# StepperBoard.net
KiCad netlist of a schematic drawn in EAGLE
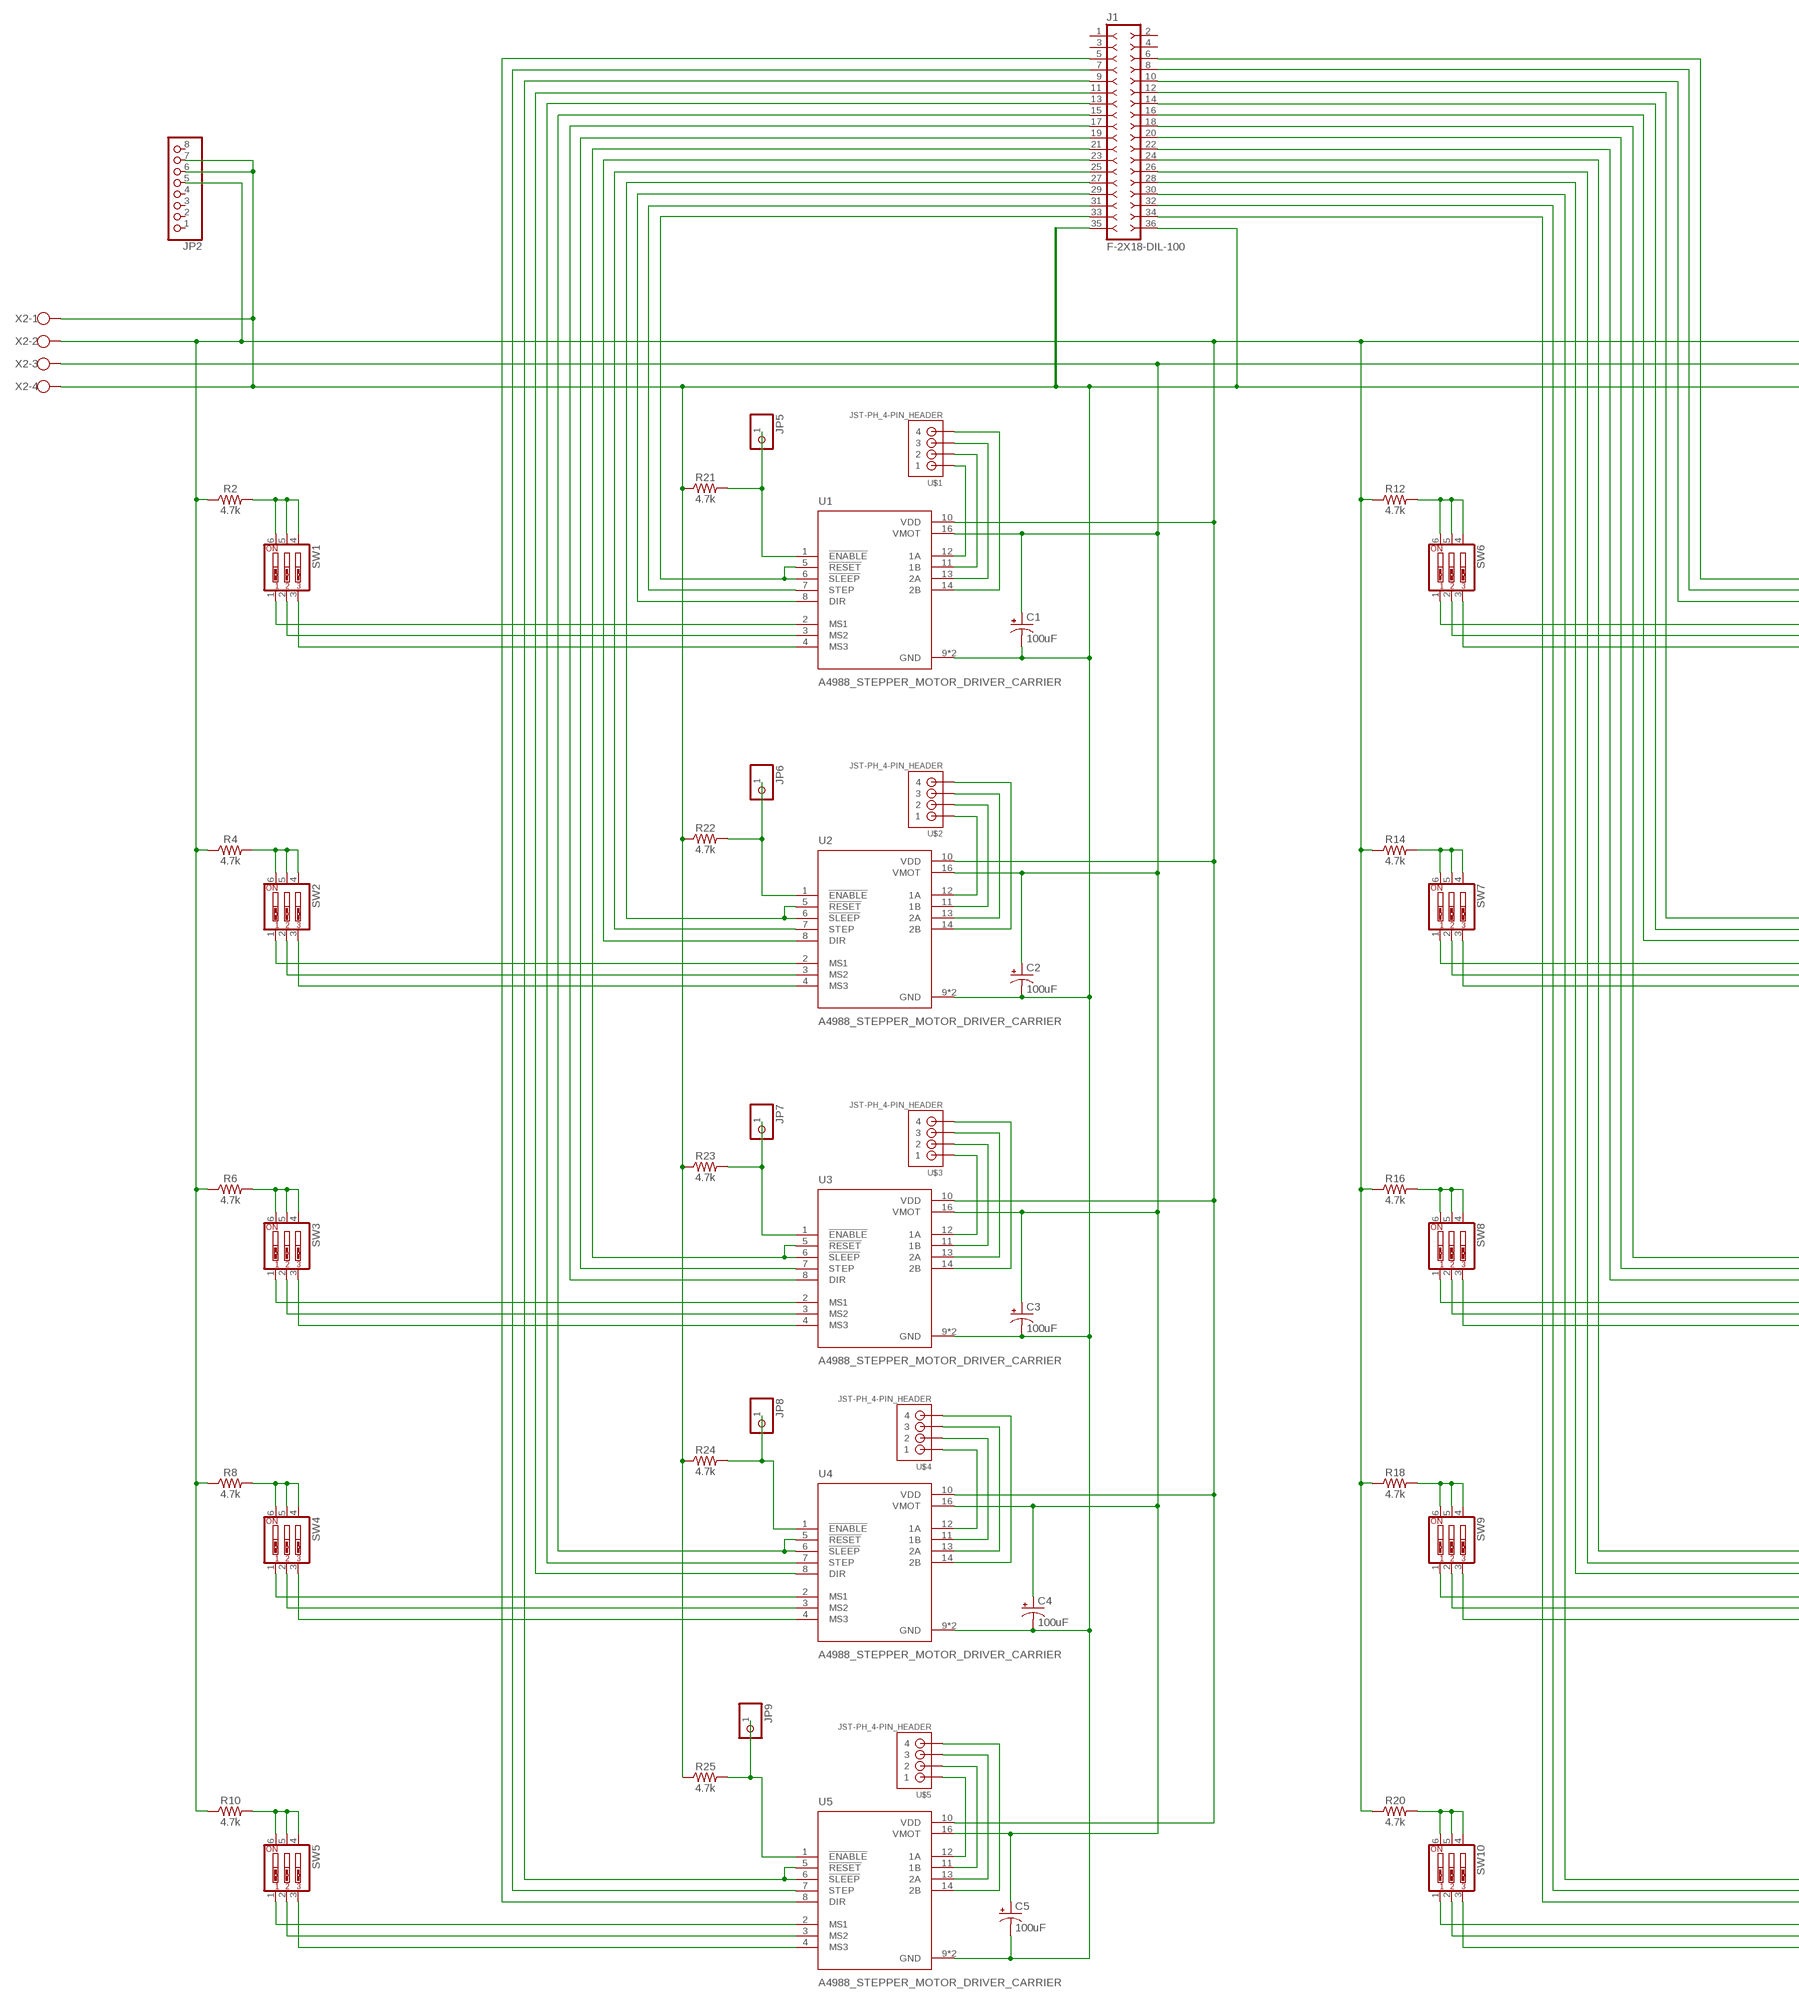
[diagram p0: schematic, sheet 1, part 1 of 2]
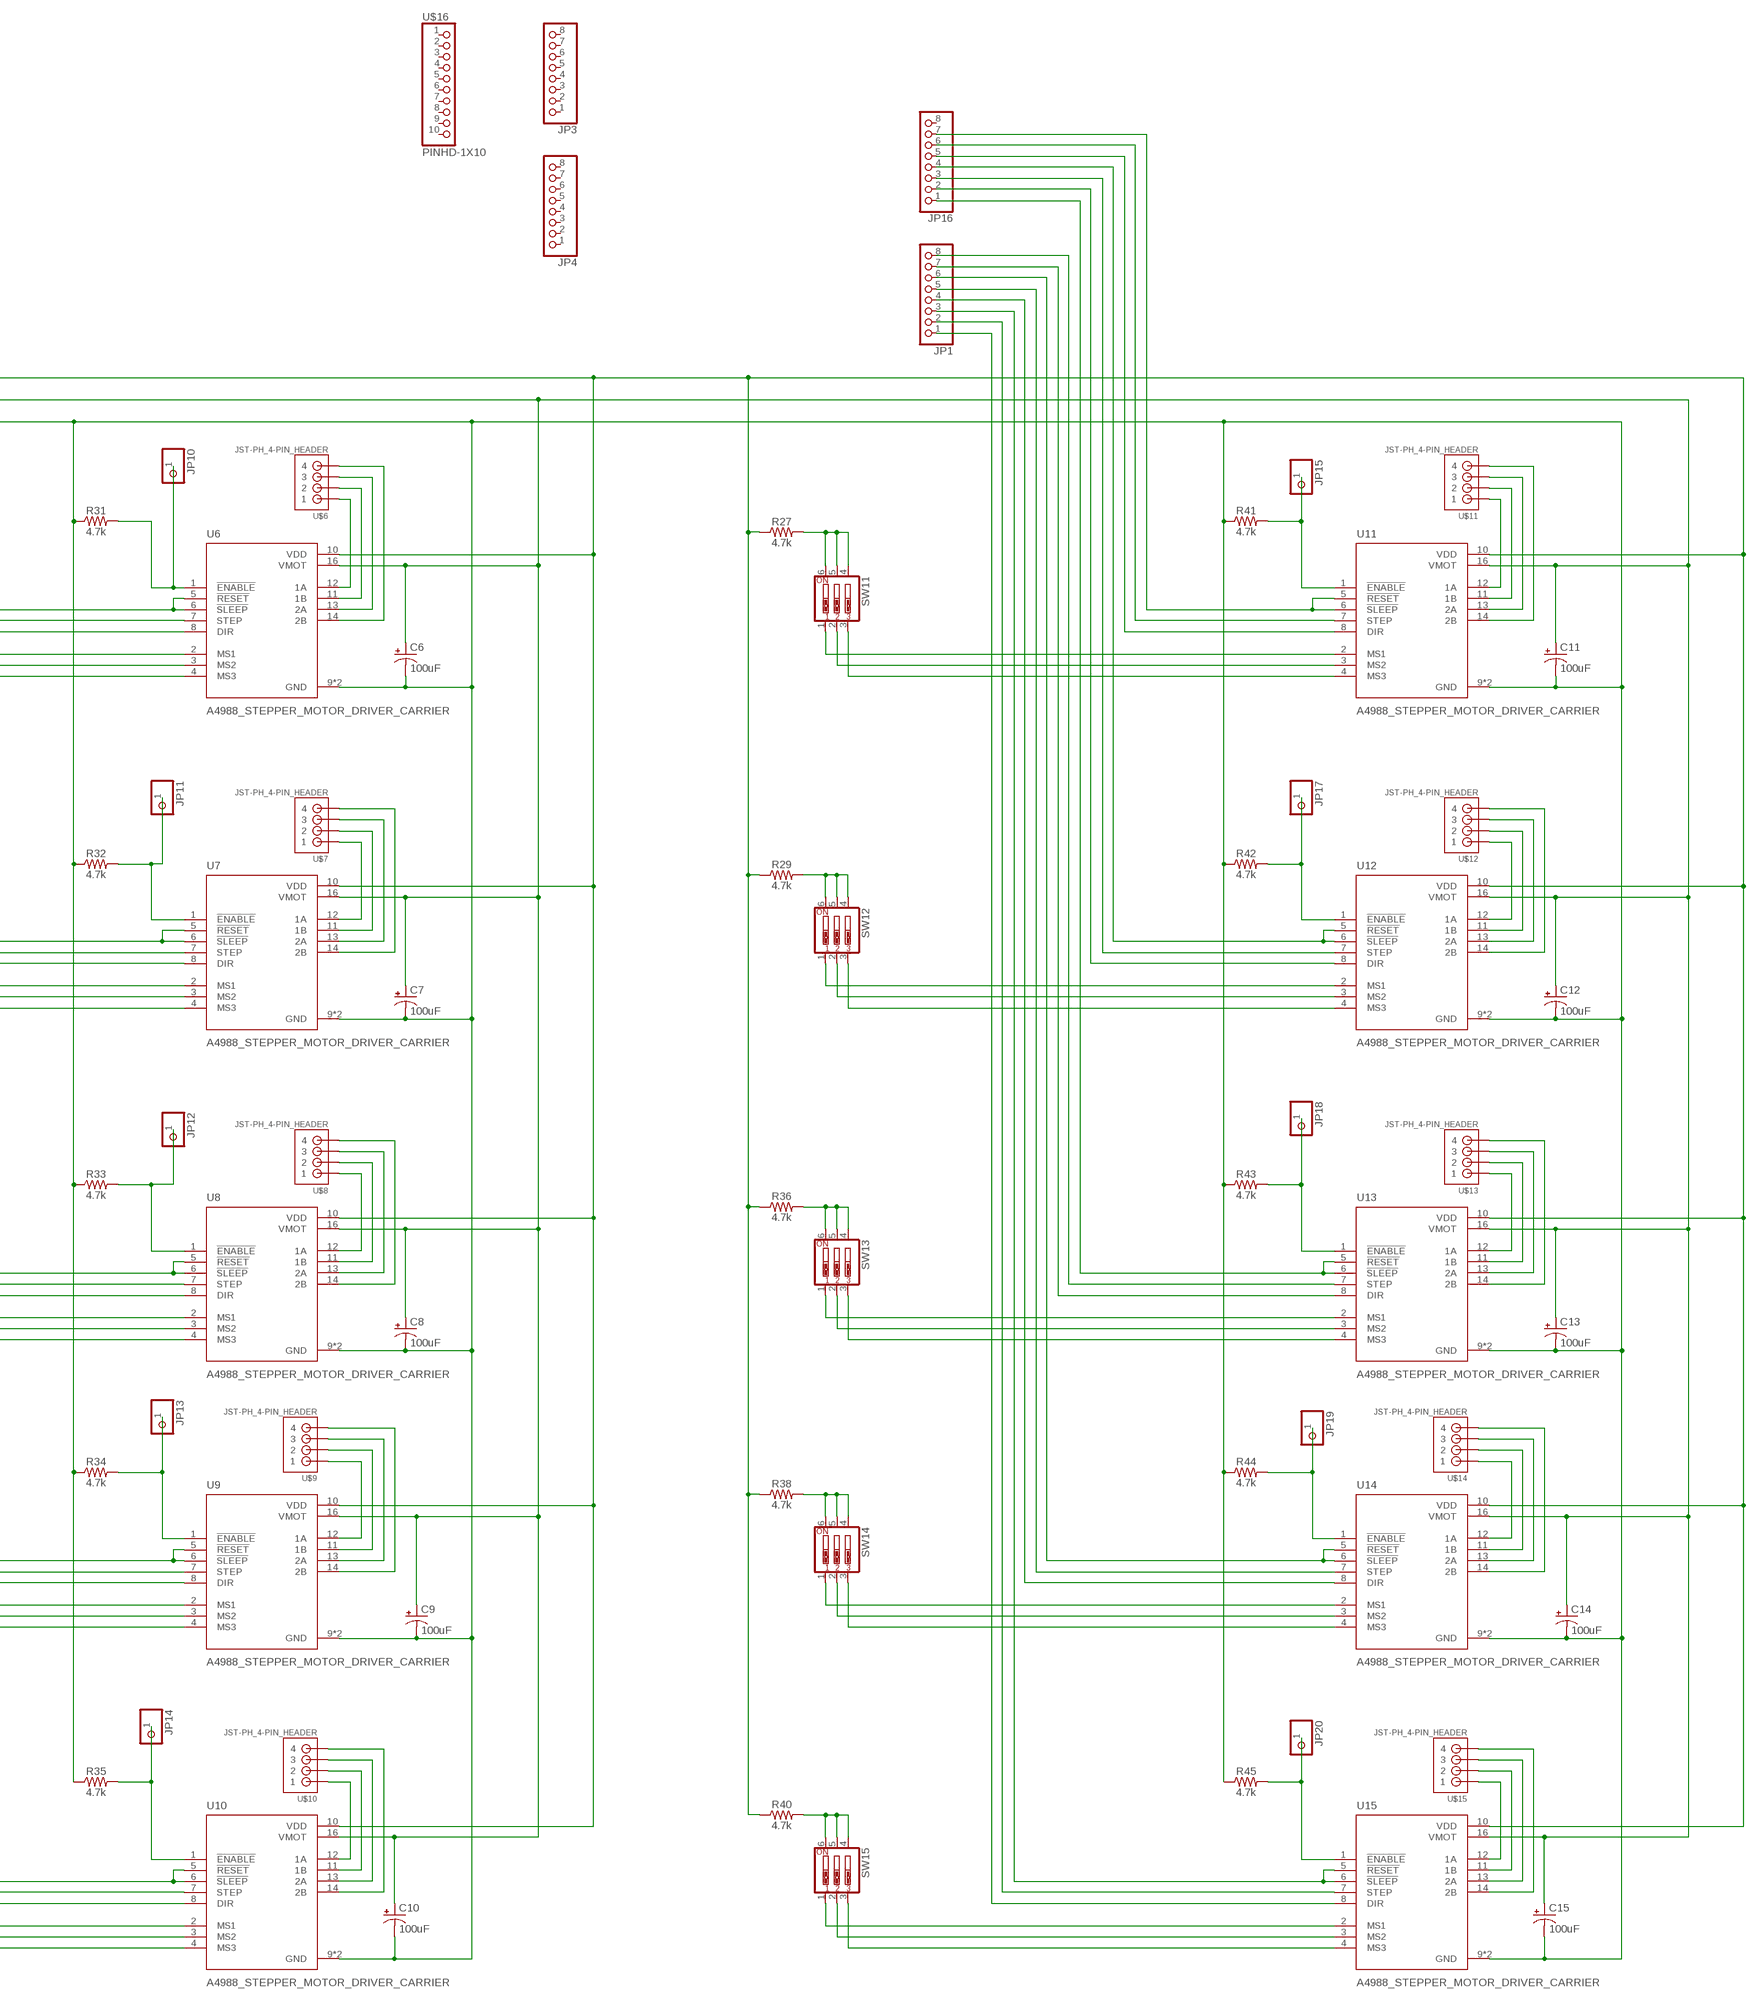
[diagram p1: schematic, sheet 1, part 2 of 2]

(export (version "E")
  (design (tool "Eeschema 10.0.6"))
  (components
    (comp (ref "C1")
      (value "100uF")
      (footprint "eagle-import:CPOL-RADIAL-2.5MM-6.5MM")
      (libsource (lib "eagle-import") (part "100UF-POLAR-RADIAL-2.5MM-25V-20%"))
    )
    (comp (ref "C2")
      (value "100uF")
      (footprint "eagle-import:CPOL-RADIAL-2.5MM-6.5MM")
      (libsource (lib "eagle-import") (part "100UF-POLAR-RADIAL-2.5MM-25V-20%"))
    )
    (comp (ref "C3")
      (value "100uF")
      (footprint "eagle-import:CPOL-RADIAL-2.5MM-6.5MM")
      (libsource (lib "eagle-import") (part "100UF-POLAR-RADIAL-2.5MM-25V-20%"))
    )
    (comp (ref "C4")
      (value "100uF")
      (footprint "eagle-import:CPOL-RADIAL-2.5MM-6.5MM")
      (libsource (lib "eagle-import") (part "100UF-POLAR-RADIAL-2.5MM-25V-20%"))
    )
    (comp (ref "C5")
      (value "100uF")
      (footprint "eagle-import:CPOL-RADIAL-2.5MM-6.5MM")
      (libsource (lib "eagle-import") (part "100UF-POLAR-RADIAL-2.5MM-25V-20%"))
    )
    (comp (ref "C6")
      (value "100uF")
      (footprint "eagle-import:CPOL-RADIAL-2.5MM-6.5MM")
      (libsource (lib "eagle-import") (part "100UF-POLAR-RADIAL-2.5MM-25V-20%"))
    )
    (comp (ref "C7")
      (value "100uF")
      (footprint "eagle-import:CPOL-RADIAL-2.5MM-6.5MM")
      (libsource (lib "eagle-import") (part "100UF-POLAR-RADIAL-2.5MM-25V-20%"))
    )
    (comp (ref "C8")
      (value "100uF")
      (footprint "eagle-import:CPOL-RADIAL-2.5MM-6.5MM")
      (libsource (lib "eagle-import") (part "100UF-POLAR-RADIAL-2.5MM-25V-20%"))
    )
    (comp (ref "C9")
      (value "100uF")
      (footprint "eagle-import:CPOL-RADIAL-2.5MM-6.5MM")
      (libsource (lib "eagle-import") (part "100UF-POLAR-RADIAL-2.5MM-25V-20%"))
    )
    (comp (ref "C10")
      (value "100uF")
      (footprint "eagle-import:CPOL-RADIAL-2.5MM-6.5MM")
      (libsource (lib "eagle-import") (part "100UF-POLAR-RADIAL-2.5MM-25V-20%"))
    )
    (comp (ref "C11")
      (value "100uF")
      (footprint "eagle-import:CPOL-RADIAL-2.5MM-6.5MM")
      (libsource (lib "eagle-import") (part "100UF-POLAR-RADIAL-2.5MM-25V-20%"))
    )
    (comp (ref "C12")
      (value "100uF")
      (footprint "eagle-import:CPOL-RADIAL-2.5MM-6.5MM")
      (libsource (lib "eagle-import") (part "100UF-POLAR-RADIAL-2.5MM-25V-20%"))
    )
    (comp (ref "C13")
      (value "100uF")
      (footprint "eagle-import:CPOL-RADIAL-2.5MM-6.5MM")
      (libsource (lib "eagle-import") (part "100UF-POLAR-RADIAL-2.5MM-25V-20%"))
    )
    (comp (ref "C14")
      (value "100uF")
      (footprint "eagle-import:CPOL-RADIAL-2.5MM-6.5MM")
      (libsource (lib "eagle-import") (part "100UF-POLAR-RADIAL-2.5MM-25V-20%"))
    )
    (comp (ref "C15")
      (value "100uF")
      (footprint "eagle-import:CPOL-RADIAL-2.5MM-6.5MM")
      (libsource (lib "eagle-import") (part "100UF-POLAR-RADIAL-2.5MM-25V-20%"))
    )
    (comp (ref "J1")
      (value "F-2X18-DIL-100")
      (footprint "eagle-import:DIL-100-2X18")
      (libsource (lib "eagle-import") (part "F-2X18-DIL-100"))
    )
    (comp (ref "JP1")
      (value "PINHD-1X8")
      (footprint "eagle-import:1X08")
      (libsource (lib "eagle-import") (part "PINHD-1X8"))
    )
    (comp (ref "JP2")
      (value "PINHD-1X8")
      (footprint "eagle-import:1X08")
      (libsource (lib "eagle-import") (part "PINHD-1X8"))
    )
    (comp (ref "JP3")
      (value "PINHD-1X8")
      (footprint "eagle-import:1X08")
      (libsource (lib "eagle-import") (part "PINHD-1X8"))
    )
    (comp (ref "JP4")
      (value "PINHD-1X8")
      (footprint "eagle-import:1X08")
      (libsource (lib "eagle-import") (part "PINHD-1X8"))
    )
    (comp (ref "JP5")
      (value "PINHD-1X1")
      (footprint "eagle-import:1X01")
      (libsource (lib "eagle-import") (part "PINHD-1X1"))
    )
    (comp (ref "JP6")
      (value "PINHD-1X1")
      (footprint "eagle-import:1X01")
      (libsource (lib "eagle-import") (part "PINHD-1X1"))
    )
    (comp (ref "JP7")
      (value "PINHD-1X1")
      (footprint "eagle-import:1X01")
      (libsource (lib "eagle-import") (part "PINHD-1X1"))
    )
    (comp (ref "JP8")
      (value "PINHD-1X1")
      (footprint "eagle-import:1X01")
      (libsource (lib "eagle-import") (part "PINHD-1X1"))
    )
    (comp (ref "JP9")
      (value "PINHD-1X1")
      (footprint "eagle-import:1X01")
      (libsource (lib "eagle-import") (part "PINHD-1X1"))
    )
    (comp (ref "JP10")
      (value "PINHD-1X1")
      (footprint "eagle-import:1X01")
      (libsource (lib "eagle-import") (part "PINHD-1X1"))
    )
    (comp (ref "JP11")
      (value "PINHD-1X1")
      (footprint "eagle-import:1X01")
      (libsource (lib "eagle-import") (part "PINHD-1X1"))
    )
    (comp (ref "JP12")
      (value "PINHD-1X1")
      (footprint "eagle-import:1X01")
      (libsource (lib "eagle-import") (part "PINHD-1X1"))
    )
    (comp (ref "JP13")
      (value "PINHD-1X1")
      (footprint "eagle-import:1X01")
      (libsource (lib "eagle-import") (part "PINHD-1X1"))
    )
    (comp (ref "JP14")
      (value "PINHD-1X1")
      (footprint "eagle-import:1X01")
      (libsource (lib "eagle-import") (part "PINHD-1X1"))
    )
    (comp (ref "JP15")
      (value "PINHD-1X1")
      (footprint "eagle-import:1X01")
      (libsource (lib "eagle-import") (part "PINHD-1X1"))
    )
    (comp (ref "JP16")
      (value "PINHD-1X8")
      (footprint "eagle-import:1X08")
      (libsource (lib "eagle-import") (part "PINHD-1X8"))
    )
    (comp (ref "JP17")
      (value "PINHD-1X1")
      (footprint "eagle-import:1X01")
      (libsource (lib "eagle-import") (part "PINHD-1X1"))
    )
    (comp (ref "JP18")
      (value "PINHD-1X1")
      (footprint "eagle-import:1X01")
      (libsource (lib "eagle-import") (part "PINHD-1X1"))
    )
    (comp (ref "JP19")
      (value "PINHD-1X1")
      (footprint "eagle-import:1X01")
      (libsource (lib "eagle-import") (part "PINHD-1X1"))
    )
    (comp (ref "JP20")
      (value "PINHD-1X1")
      (footprint "eagle-import:1X01")
      (libsource (lib "eagle-import") (part "PINHD-1X1"))
    )
    (comp (ref "R2")
      (value "4.7k")
      (footprint "eagle-import:0603")
      (libsource (lib "eagle-import") (part "4.7KOHM-0603-1/10W-1%"))
    )
    (comp (ref "R4")
      (value "4.7k")
      (footprint "eagle-import:0603")
      (libsource (lib "eagle-import") (part "4.7KOHM-0603-1/10W-1%"))
    )
    (comp (ref "R6")
      (value "4.7k")
      (footprint "eagle-import:0603")
      (libsource (lib "eagle-import") (part "4.7KOHM-0603-1/10W-1%"))
    )
    (comp (ref "R8")
      (value "4.7k")
      (footprint "eagle-import:0603")
      (libsource (lib "eagle-import") (part "4.7KOHM-0603-1/10W-1%"))
    )
    (comp (ref "R10")
      (value "4.7k")
      (footprint "eagle-import:0603")
      (libsource (lib "eagle-import") (part "4.7KOHM-0603-1/10W-1%"))
    )
    (comp (ref "R12")
      (value "4.7k")
      (footprint "eagle-import:0603")
      (libsource (lib "eagle-import") (part "4.7KOHM-0603-1/10W-1%"))
    )
    (comp (ref "R14")
      (value "4.7k")
      (footprint "eagle-import:0603")
      (libsource (lib "eagle-import") (part "4.7KOHM-0603-1/10W-1%"))
    )
    (comp (ref "R16")
      (value "4.7k")
      (footprint "eagle-import:0603")
      (libsource (lib "eagle-import") (part "4.7KOHM-0603-1/10W-1%"))
    )
    (comp (ref "R18")
      (value "4.7k")
      (footprint "eagle-import:0603")
      (libsource (lib "eagle-import") (part "4.7KOHM-0603-1/10W-1%"))
    )
    (comp (ref "R20")
      (value "4.7k")
      (footprint "eagle-import:0603")
      (libsource (lib "eagle-import") (part "4.7KOHM-0603-1/10W-1%"))
    )
    (comp (ref "R21")
      (value "4.7k")
      (footprint "eagle-import:0603")
      (libsource (lib "eagle-import") (part "4.7KOHM-0603-1/10W-1%"))
    )
    (comp (ref "R22")
      (value "4.7k")
      (footprint "eagle-import:0603")
      (libsource (lib "eagle-import") (part "4.7KOHM-0603-1/10W-1%"))
    )
    (comp (ref "R23")
      (value "4.7k")
      (footprint "eagle-import:0603")
      (libsource (lib "eagle-import") (part "4.7KOHM-0603-1/10W-1%"))
    )
    (comp (ref "R24")
      (value "4.7k")
      (footprint "eagle-import:0603")
      (libsource (lib "eagle-import") (part "4.7KOHM-0603-1/10W-1%"))
    )
    (comp (ref "R25")
      (value "4.7k")
      (footprint "eagle-import:0603")
      (libsource (lib "eagle-import") (part "4.7KOHM-0603-1/10W-1%"))
    )
    (comp (ref "R27")
      (value "4.7k")
      (footprint "eagle-import:0603")
      (libsource (lib "eagle-import") (part "4.7KOHM-0603-1/10W-1%"))
    )
    (comp (ref "R29")
      (value "4.7k")
      (footprint "eagle-import:0603")
      (libsource (lib "eagle-import") (part "4.7KOHM-0603-1/10W-1%"))
    )
    (comp (ref "R31")
      (value "4.7k")
      (footprint "eagle-import:0603")
      (libsource (lib "eagle-import") (part "4.7KOHM-0603-1/10W-1%"))
    )
    (comp (ref "R32")
      (value "4.7k")
      (footprint "eagle-import:0603")
      (libsource (lib "eagle-import") (part "4.7KOHM-0603-1/10W-1%"))
    )
    (comp (ref "R33")
      (value "4.7k")
      (footprint "eagle-import:0603")
      (libsource (lib "eagle-import") (part "4.7KOHM-0603-1/10W-1%"))
    )
    (comp (ref "R34")
      (value "4.7k")
      (footprint "eagle-import:0603")
      (libsource (lib "eagle-import") (part "4.7KOHM-0603-1/10W-1%"))
    )
    (comp (ref "R35")
      (value "4.7k")
      (footprint "eagle-import:0603")
      (libsource (lib "eagle-import") (part "4.7KOHM-0603-1/10W-1%"))
    )
    (comp (ref "R36")
      (value "4.7k")
      (footprint "eagle-import:0603")
      (libsource (lib "eagle-import") (part "4.7KOHM-0603-1/10W-1%"))
    )
    (comp (ref "R38")
      (value "4.7k")
      (footprint "eagle-import:0603")
      (libsource (lib "eagle-import") (part "4.7KOHM-0603-1/10W-1%"))
    )
    (comp (ref "R40")
      (value "4.7k")
      (footprint "eagle-import:0603")
      (libsource (lib "eagle-import") (part "4.7KOHM-0603-1/10W-1%"))
    )
    (comp (ref "R41")
      (value "4.7k")
      (footprint "eagle-import:0603")
      (libsource (lib "eagle-import") (part "4.7KOHM-0603-1/10W-1%"))
    )
    (comp (ref "R42")
      (value "4.7k")
      (footprint "eagle-import:0603")
      (libsource (lib "eagle-import") (part "4.7KOHM-0603-1/10W-1%"))
    )
    (comp (ref "R43")
      (value "4.7k")
      (footprint "eagle-import:0603")
      (libsource (lib "eagle-import") (part "4.7KOHM-0603-1/10W-1%"))
    )
    (comp (ref "R44")
      (value "4.7k")
      (footprint "eagle-import:0603")
      (libsource (lib "eagle-import") (part "4.7KOHM-0603-1/10W-1%"))
    )
    (comp (ref "R45")
      (value "4.7k")
      (footprint "eagle-import:0603")
      (libsource (lib "eagle-import") (part "4.7KOHM-0603-1/10W-1%"))
    )
    (comp (ref "SW1")
      (value "SW_DIP-3")
      (footprint "eagle-import:EDG-03")
      (libsource (lib "eagle-import") (part "SW_DIP-3"))
    )
    (comp (ref "SW2")
      (value "SW_DIP-3")
      (footprint "eagle-import:EDG-03")
      (libsource (lib "eagle-import") (part "SW_DIP-3"))
    )
    (comp (ref "SW3")
      (value "SW_DIP-3")
      (footprint "eagle-import:EDG-03")
      (libsource (lib "eagle-import") (part "SW_DIP-3"))
    )
    (comp (ref "SW4")
      (value "SW_DIP-3")
      (footprint "eagle-import:EDG-03")
      (libsource (lib "eagle-import") (part "SW_DIP-3"))
    )
    (comp (ref "SW5")
      (value "SW_DIP-3")
      (footprint "eagle-import:EDG-03")
      (libsource (lib "eagle-import") (part "SW_DIP-3"))
    )
    (comp (ref "SW6")
      (value "SW_DIP-3")
      (footprint "eagle-import:EDG-03")
      (libsource (lib "eagle-import") (part "SW_DIP-3"))
    )
    (comp (ref "SW7")
      (value "SW_DIP-3")
      (footprint "eagle-import:EDG-03")
      (libsource (lib "eagle-import") (part "SW_DIP-3"))
    )
    (comp (ref "SW8")
      (value "SW_DIP-3")
      (footprint "eagle-import:EDG-03")
      (libsource (lib "eagle-import") (part "SW_DIP-3"))
    )
    (comp (ref "SW9")
      (value "SW_DIP-3")
      (footprint "eagle-import:EDG-03")
      (libsource (lib "eagle-import") (part "SW_DIP-3"))
    )
    (comp (ref "SW10")
      (value "SW_DIP-3")
      (footprint "eagle-import:EDG-03")
      (libsource (lib "eagle-import") (part "SW_DIP-3"))
    )
    (comp (ref "SW11")
      (value "SW_DIP-3")
      (footprint "eagle-import:EDG-03")
      (libsource (lib "eagle-import") (part "SW_DIP-3"))
    )
    (comp (ref "SW12")
      (value "SW_DIP-3")
      (footprint "eagle-import:EDG-03")
      (libsource (lib "eagle-import") (part "SW_DIP-3"))
    )
    (comp (ref "SW13")
      (value "SW_DIP-3")
      (footprint "eagle-import:EDG-03")
      (libsource (lib "eagle-import") (part "SW_DIP-3"))
    )
    (comp (ref "SW14")
      (value "SW_DIP-3")
      (footprint "eagle-import:EDG-03")
      (libsource (lib "eagle-import") (part "SW_DIP-3"))
    )
    (comp (ref "SW15")
      (value "SW_DIP-3")
      (footprint "eagle-import:EDG-03")
      (libsource (lib "eagle-import") (part "SW_DIP-3"))
    )
    (comp (ref "U$1")
      (value "JST-PH_4-PIN_HEADER")
      (footprint "eagle-import:JST_B4B-PH_HEADER")
      (libsource (lib "eagle-import") (part "JST-PH_4-PIN_HEADER"))
    )
    (comp (ref "U$2")
      (value "JST-PH_4-PIN_HEADER")
      (footprint "eagle-import:JST_B4B-PH_HEADER")
      (libsource (lib "eagle-import") (part "JST-PH_4-PIN_HEADER"))
    )
    (comp (ref "U$3")
      (value "JST-PH_4-PIN_HEADER")
      (footprint "eagle-import:JST_B4B-PH_HEADER")
      (libsource (lib "eagle-import") (part "JST-PH_4-PIN_HEADER"))
    )
    (comp (ref "U$4")
      (value "JST-PH_4-PIN_HEADER")
      (footprint "eagle-import:JST_B4B-PH_HEADER")
      (libsource (lib "eagle-import") (part "JST-PH_4-PIN_HEADER"))
    )
    (comp (ref "U$5")
      (value "JST-PH_4-PIN_HEADER")
      (footprint "eagle-import:JST_B4B-PH_HEADER")
      (libsource (lib "eagle-import") (part "JST-PH_4-PIN_HEADER"))
    )
    (comp (ref "U$6")
      (value "JST-PH_4-PIN_HEADER")
      (footprint "eagle-import:JST_B4B-PH_HEADER")
      (libsource (lib "eagle-import") (part "JST-PH_4-PIN_HEADER"))
    )
    (comp (ref "U$7")
      (value "JST-PH_4-PIN_HEADER")
      (footprint "eagle-import:JST_B4B-PH_HEADER")
      (libsource (lib "eagle-import") (part "JST-PH_4-PIN_HEADER"))
    )
    (comp (ref "U$8")
      (value "JST-PH_4-PIN_HEADER")
      (footprint "eagle-import:JST_B4B-PH_HEADER")
      (libsource (lib "eagle-import") (part "JST-PH_4-PIN_HEADER"))
    )
    (comp (ref "U$9")
      (value "JST-PH_4-PIN_HEADER")
      (footprint "eagle-import:JST_B4B-PH_HEADER")
      (libsource (lib "eagle-import") (part "JST-PH_4-PIN_HEADER"))
    )
    (comp (ref "U$10")
      (value "JST-PH_4-PIN_HEADER")
      (footprint "eagle-import:JST_B4B-PH_HEADER")
      (libsource (lib "eagle-import") (part "JST-PH_4-PIN_HEADER"))
    )
    (comp (ref "U$11")
      (value "JST-PH_4-PIN_HEADER")
      (footprint "eagle-import:JST_B4B-PH_HEADER")
      (libsource (lib "eagle-import") (part "JST-PH_4-PIN_HEADER"))
    )
    (comp (ref "U$12")
      (value "JST-PH_4-PIN_HEADER")
      (footprint "eagle-import:JST_B4B-PH_HEADER")
      (libsource (lib "eagle-import") (part "JST-PH_4-PIN_HEADER"))
    )
    (comp (ref "U$13")
      (value "JST-PH_4-PIN_HEADER")
      (footprint "eagle-import:JST_B4B-PH_HEADER")
      (libsource (lib "eagle-import") (part "JST-PH_4-PIN_HEADER"))
    )
    (comp (ref "U$14")
      (value "JST-PH_4-PIN_HEADER")
      (footprint "eagle-import:JST_B4B-PH_HEADER")
      (libsource (lib "eagle-import") (part "JST-PH_4-PIN_HEADER"))
    )
    (comp (ref "U$15")
      (value "JST-PH_4-PIN_HEADER")
      (footprint "eagle-import:JST_B4B-PH_HEADER")
      (libsource (lib "eagle-import") (part "JST-PH_4-PIN_HEADER"))
    )
    (comp (ref "U$16")
      (value "PINHD-1X10")
      (footprint "eagle-import:1X10-BIG")
      (libsource (lib "eagle-import") (part "PINHD-1X10"))
    )
    (comp (ref "U1")
      (value "A4988_STEPPER_MOTOR_DRIVER_CARRIER")
      (footprint "eagle-import:MODULE_A4988_STEPPER_MOTOR_DRIVER_CARRIER")
      (fields (field (name "MF") "Pololu") (field (name "MP") "A4988 STEPPER MOTOR DRIVER CARRIER"))
      (libsource (lib "eagle-import") (part "A4988_STEPPER_MOTOR_DRIVER_CARRIER"))
    )
    (comp (ref "U2")
      (value "A4988_STEPPER_MOTOR_DRIVER_CARRIER")
      (footprint "eagle-import:MODULE_A4988_STEPPER_MOTOR_DRIVER_CARRIER")
      (fields (field (name "MF") "Pololu") (field (name "MP") "A4988 STEPPER MOTOR DRIVER CARRIER"))
      (libsource (lib "eagle-import") (part "A4988_STEPPER_MOTOR_DRIVER_CARRIER"))
    )
    (comp (ref "U3")
      (value "A4988_STEPPER_MOTOR_DRIVER_CARRIER")
      (footprint "eagle-import:MODULE_A4988_STEPPER_MOTOR_DRIVER_CARRIER")
      (fields (field (name "MF") "Pololu") (field (name "MP") "A4988 STEPPER MOTOR DRIVER CARRIER"))
      (libsource (lib "eagle-import") (part "A4988_STEPPER_MOTOR_DRIVER_CARRIER"))
    )
    (comp (ref "U4")
      (value "A4988_STEPPER_MOTOR_DRIVER_CARRIER")
      (footprint "eagle-import:MODULE_A4988_STEPPER_MOTOR_DRIVER_CARRIER")
      (fields (field (name "MF") "Pololu") (field (name "MP") "A4988 STEPPER MOTOR DRIVER CARRIER"))
      (libsource (lib "eagle-import") (part "A4988_STEPPER_MOTOR_DRIVER_CARRIER"))
    )
    (comp (ref "U5")
      (value "A4988_STEPPER_MOTOR_DRIVER_CARRIER")
      (footprint "eagle-import:MODULE_A4988_STEPPER_MOTOR_DRIVER_CARRIER")
      (fields (field (name "MF") "Pololu") (field (name "MP") "A4988 STEPPER MOTOR DRIVER CARRIER"))
      (libsource (lib "eagle-import") (part "A4988_STEPPER_MOTOR_DRIVER_CARRIER"))
    )
    (comp (ref "U6")
      (value "A4988_STEPPER_MOTOR_DRIVER_CARRIER")
      (footprint "eagle-import:MODULE_A4988_STEPPER_MOTOR_DRIVER_CARRIER")
      (fields (field (name "MF") "Pololu") (field (name "MP") "A4988 STEPPER MOTOR DRIVER CARRIER"))
      (libsource (lib "eagle-import") (part "A4988_STEPPER_MOTOR_DRIVER_CARRIER"))
    )
    (comp (ref "U7")
      (value "A4988_STEPPER_MOTOR_DRIVER_CARRIER")
      (footprint "eagle-import:MODULE_A4988_STEPPER_MOTOR_DRIVER_CARRIER")
      (fields (field (name "MF") "Pololu") (field (name "MP") "A4988 STEPPER MOTOR DRIVER CARRIER"))
      (libsource (lib "eagle-import") (part "A4988_STEPPER_MOTOR_DRIVER_CARRIER"))
    )
    (comp (ref "U8")
      (value "A4988_STEPPER_MOTOR_DRIVER_CARRIER")
      (footprint "eagle-import:MODULE_A4988_STEPPER_MOTOR_DRIVER_CARRIER")
      (fields (field (name "MF") "Pololu") (field (name "MP") "A4988 STEPPER MOTOR DRIVER CARRIER"))
      (libsource (lib "eagle-import") (part "A4988_STEPPER_MOTOR_DRIVER_CARRIER"))
    )
    (comp (ref "U9")
      (value "A4988_STEPPER_MOTOR_DRIVER_CARRIER")
      (footprint "eagle-import:MODULE_A4988_STEPPER_MOTOR_DRIVER_CARRIER")
      (fields (field (name "MF") "Pololu") (field (name "MP") "A4988 STEPPER MOTOR DRIVER CARRIER"))
      (libsource (lib "eagle-import") (part "A4988_STEPPER_MOTOR_DRIVER_CARRIER"))
    )
    (comp (ref "U10")
      (value "A4988_STEPPER_MOTOR_DRIVER_CARRIER")
      (footprint "eagle-import:MODULE_A4988_STEPPER_MOTOR_DRIVER_CARRIER")
      (fields (field (name "MF") "Pololu") (field (name "MP") "A4988 STEPPER MOTOR DRIVER CARRIER"))
      (libsource (lib "eagle-import") (part "A4988_STEPPER_MOTOR_DRIVER_CARRIER"))
    )
    (comp (ref "U11")
      (value "A4988_STEPPER_MOTOR_DRIVER_CARRIER")
      (footprint "eagle-import:MODULE_A4988_STEPPER_MOTOR_DRIVER_CARRIER")
      (fields (field (name "MF") "Pololu") (field (name "MP") "A4988 STEPPER MOTOR DRIVER CARRIER"))
      (libsource (lib "eagle-import") (part "A4988_STEPPER_MOTOR_DRIVER_CARRIER"))
    )
    (comp (ref "U12")
      (value "A4988_STEPPER_MOTOR_DRIVER_CARRIER")
      (footprint "eagle-import:MODULE_A4988_STEPPER_MOTOR_DRIVER_CARRIER")
      (fields (field (name "MF") "Pololu") (field (name "MP") "A4988 STEPPER MOTOR DRIVER CARRIER"))
      (libsource (lib "eagle-import") (part "A4988_STEPPER_MOTOR_DRIVER_CARRIER"))
    )
    (comp (ref "U13")
      (value "A4988_STEPPER_MOTOR_DRIVER_CARRIER")
      (footprint "eagle-import:MODULE_A4988_STEPPER_MOTOR_DRIVER_CARRIER")
      (fields (field (name "MF") "Pololu") (field (name "MP") "A4988 STEPPER MOTOR DRIVER CARRIER"))
      (libsource (lib "eagle-import") (part "A4988_STEPPER_MOTOR_DRIVER_CARRIER"))
    )
    (comp (ref "U14")
      (value "A4988_STEPPER_MOTOR_DRIVER_CARRIER")
      (footprint "eagle-import:MODULE_A4988_STEPPER_MOTOR_DRIVER_CARRIER")
      (fields (field (name "MF") "Pololu") (field (name "MP") "A4988 STEPPER MOTOR DRIVER CARRIER"))
      (libsource (lib "eagle-import") (part "A4988_STEPPER_MOTOR_DRIVER_CARRIER"))
    )
    (comp (ref "U15")
      (value "A4988_STEPPER_MOTOR_DRIVER_CARRIER")
      (footprint "eagle-import:MODULE_A4988_STEPPER_MOTOR_DRIVER_CARRIER")
      (fields (field (name "MF") "Pololu") (field (name "MP") "A4988 STEPPER MOTOR DRIVER CARRIER"))
      (libsource (lib "eagle-import") (part "A4988_STEPPER_MOTOR_DRIVER_CARRIER"))
    )
    (comp (ref "X2")
      (value "W237-4")
      (footprint "eagle-import:W237-4")
      (libsource (lib "eagle-import") (part "W237-4"))
    )
  )
  (nets
    (net (code "1") (name "Net-(C1-+)") (class "Default")
      (node (ref "C1") (pin "1") (pinfunction "+_1") (pintype "passive"))
      (node (ref "C10") (pin "1") (pinfunction "+_1") (pintype "passive"))
      (node (ref "C11") (pin "1") (pinfunction "+_1") (pintype "passive"))
      (node (ref "C12") (pin "1") (pinfunction "+_1") (pintype "passive"))
      (node (ref "C13") (pin "1") (pinfunction "+_1") (pintype "passive"))
      (node (ref "C14") (pin "1") (pinfunction "+_1") (pintype "passive"))
      (node (ref "C15") (pin "1") (pinfunction "+_1") (pintype "passive"))
      (node (ref "C2") (pin "1") (pinfunction "+_1") (pintype "passive"))
      (node (ref "C3") (pin "1") (pinfunction "+_1") (pintype "passive"))
      (node (ref "C4") (pin "1") (pinfunction "+_1") (pintype "passive"))
      (node (ref "C5") (pin "1") (pinfunction "+_1") (pintype "passive"))
      (node (ref "C6") (pin "1") (pinfunction "+_1") (pintype "passive"))
      (node (ref "C7") (pin "1") (pinfunction "+_1") (pintype "passive"))
      (node (ref "C8") (pin "1") (pinfunction "+_1") (pintype "passive"))
      (node (ref "C9") (pin "1") (pinfunction "+_1") (pintype "passive"))
      (node (ref "U1") (pin "16") (pinfunction "VMOT_16") (pintype "power_in"))
      (node (ref "U10") (pin "16") (pinfunction "VMOT_16") (pintype "power_in"))
      (node (ref "U11") (pin "16") (pinfunction "VMOT_16") (pintype "power_in"))
      (node (ref "U12") (pin "16") (pinfunction "VMOT_16") (pintype "power_in"))
      (node (ref "U13") (pin "16") (pinfunction "VMOT_16") (pintype "power_in"))
      (node (ref "U14") (pin "16") (pinfunction "VMOT_16") (pintype "power_in"))
      (node (ref "U15") (pin "16") (pinfunction "VMOT_16") (pintype "power_in"))
      (node (ref "U2") (pin "16") (pinfunction "VMOT_16") (pintype "power_in"))
      (node (ref "U3") (pin "16") (pinfunction "VMOT_16") (pintype "power_in"))
      (node (ref "U4") (pin "16") (pinfunction "VMOT_16") (pintype "power_in"))
      (node (ref "U5") (pin "16") (pinfunction "VMOT_16") (pintype "power_in"))
      (node (ref "U6") (pin "16") (pinfunction "VMOT_16") (pintype "power_in"))
      (node (ref "U7") (pin "16") (pinfunction "VMOT_16") (pintype "power_in"))
      (node (ref "U8") (pin "16") (pinfunction "VMOT_16") (pintype "power_in"))
      (node (ref "U9") (pin "16") (pinfunction "VMOT_16") (pintype "power_in"))
      (node (ref "X2") (pin "3") (pinfunction "KL_3") (pintype "passive"))
    )
    (net (code "2") (name "Net-(C1--)") (class "Default")
      (node (ref "C1") (pin "2") (pinfunction "-_2") (pintype "passive"))
      (node (ref "C10") (pin "2") (pinfunction "-_2") (pintype "passive"))
      (node (ref "C11") (pin "2") (pinfunction "-_2") (pintype "passive"))
      (node (ref "C12") (pin "2") (pinfunction "-_2") (pintype "passive"))
      (node (ref "C13") (pin "2") (pinfunction "-_2") (pintype "passive"))
      (node (ref "C14") (pin "2") (pinfunction "-_2") (pintype "passive"))
      (node (ref "C15") (pin "2") (pinfunction "-_2") (pintype "passive"))
      (node (ref "C2") (pin "2") (pinfunction "-_2") (pintype "passive"))
      (node (ref "C3") (pin "2") (pinfunction "-_2") (pintype "passive"))
      (node (ref "C4") (pin "2") (pinfunction "-_2") (pintype "passive"))
      (node (ref "C5") (pin "2") (pinfunction "-_2") (pintype "passive"))
      (node (ref "C6") (pin "2") (pinfunction "-_2") (pintype "passive"))
      (node (ref "C7") (pin "2") (pinfunction "-_2") (pintype "passive"))
      (node (ref "C8") (pin "2") (pinfunction "-_2") (pintype "passive"))
      (node (ref "C9") (pin "2") (pinfunction "-_2") (pintype "passive"))
      (node (ref "J1") (pin "35") (pinfunction "35_35") (pintype "passive"))
      (node (ref "J1") (pin "36") (pinfunction "36_36") (pintype "passive"))
      (node (ref "JP2") (pin "6") (pinfunction "6_6") (pintype "passive"))
      (node (ref "JP2") (pin "7") (pinfunction "7_7") (pintype "passive"))
      (node (ref "R21") (pin "1") (pinfunction "1_1") (pintype "passive"))
      (node (ref "R22") (pin "1") (pinfunction "1_1") (pintype "passive"))
      (node (ref "R23") (pin "1") (pinfunction "1_1") (pintype "passive"))
      (node (ref "R24") (pin "1") (pinfunction "1_1") (pintype "passive"))
      (node (ref "R25") (pin "1") (pinfunction "1_1") (pintype "passive"))
      (node (ref "R31") (pin "1") (pinfunction "1_1") (pintype "passive"))
      (node (ref "R32") (pin "1") (pinfunction "1_1") (pintype "passive"))
      (node (ref "R33") (pin "1") (pinfunction "1_1") (pintype "passive"))
      (node (ref "R34") (pin "1") (pinfunction "1_1") (pintype "passive"))
      (node (ref "R35") (pin "1") (pinfunction "1_1") (pintype "passive"))
      (node (ref "R41") (pin "1") (pinfunction "1_1") (pintype "passive"))
      (node (ref "R42") (pin "1") (pinfunction "1_1") (pintype "passive"))
      (node (ref "R43") (pin "1") (pinfunction "1_1") (pintype "passive"))
      (node (ref "R44") (pin "1") (pinfunction "1_1") (pintype "passive"))
      (node (ref "R45") (pin "1") (pinfunction "1_1") (pintype "passive"))
      (node (ref "U1") (pin "15") (pinfunction "GND_15") (pintype "power_in"))
      (node (ref "U1") (pin "9") (pinfunction "GND_9") (pintype "power_in"))
      (node (ref "U10") (pin "15") (pinfunction "GND_15") (pintype "power_in"))
      (node (ref "U10") (pin "9") (pinfunction "GND_9") (pintype "power_in"))
      (node (ref "U11") (pin "15") (pinfunction "GND_15") (pintype "power_in"))
      (node (ref "U11") (pin "9") (pinfunction "GND_9") (pintype "power_in"))
      (node (ref "U12") (pin "15") (pinfunction "GND_15") (pintype "power_in"))
      (node (ref "U12") (pin "9") (pinfunction "GND_9") (pintype "power_in"))
      (node (ref "U13") (pin "15") (pinfunction "GND_15") (pintype "power_in"))
      (node (ref "U13") (pin "9") (pinfunction "GND_9") (pintype "power_in"))
      (node (ref "U14") (pin "15") (pinfunction "GND_15") (pintype "power_in"))
      (node (ref "U14") (pin "9") (pinfunction "GND_9") (pintype "power_in"))
      (node (ref "U15") (pin "15") (pinfunction "GND_15") (pintype "power_in"))
      (node (ref "U15") (pin "9") (pinfunction "GND_9") (pintype "power_in"))
      (node (ref "U2") (pin "15") (pinfunction "GND_15") (pintype "power_in"))
      (node (ref "U2") (pin "9") (pinfunction "GND_9") (pintype "power_in"))
      (node (ref "U3") (pin "15") (pinfunction "GND_15") (pintype "power_in"))
      (node (ref "U3") (pin "9") (pinfunction "GND_9") (pintype "power_in"))
      (node (ref "U4") (pin "15") (pinfunction "GND_15") (pintype "power_in"))
      (node (ref "U4") (pin "9") (pinfunction "GND_9") (pintype "power_in"))
      (node (ref "U5") (pin "15") (pinfunction "GND_15") (pintype "power_in"))
      (node (ref "U5") (pin "9") (pinfunction "GND_9") (pintype "power_in"))
      (node (ref "U6") (pin "15") (pinfunction "GND_15") (pintype "power_in"))
      (node (ref "U6") (pin "9") (pinfunction "GND_9") (pintype "power_in"))
      (node (ref "U7") (pin "15") (pinfunction "GND_15") (pintype "power_in"))
      (node (ref "U7") (pin "9") (pinfunction "GND_9") (pintype "power_in"))
      (node (ref "U8") (pin "15") (pinfunction "GND_15") (pintype "power_in"))
      (node (ref "U8") (pin "9") (pinfunction "GND_9") (pintype "power_in"))
      (node (ref "U9") (pin "15") (pinfunction "GND_15") (pintype "power_in"))
      (node (ref "U9") (pin "9") (pinfunction "GND_9") (pintype "power_in"))
      (node (ref "X2") (pin "1") (pinfunction "KL_1") (pintype "passive"))
      (node (ref "X2") (pin "4") (pinfunction "KL_4") (pintype "passive"))
    )
    (net (code "3") (name "Net-(R2-Pad2)") (class "Default")
      (node (ref "R2") (pin "2") (pinfunction "2_2") (pintype "passive"))
      (node (ref "SW1") (pin "4") (pinfunction "4_4") (pintype "passive"))
      (node (ref "SW1") (pin "5") (pinfunction "5_5") (pintype "passive"))
      (node (ref "SW1") (pin "6") (pinfunction "6_6") (pintype "passive"))
    )
    (net (code "4") (name "Net-(R4-Pad2)") (class "Default")
      (node (ref "R4") (pin "2") (pinfunction "2_2") (pintype "passive"))
      (node (ref "SW2") (pin "4") (pinfunction "4_4") (pintype "passive"))
      (node (ref "SW2") (pin "5") (pinfunction "5_5") (pintype "passive"))
      (node (ref "SW2") (pin "6") (pinfunction "6_6") (pintype "passive"))
    )
    (net (code "5") (name "Net-(R6-Pad2)") (class "Default")
      (node (ref "R6") (pin "2") (pinfunction "2_2") (pintype "passive"))
      (node (ref "SW3") (pin "4") (pinfunction "4_4") (pintype "passive"))
      (node (ref "SW3") (pin "5") (pinfunction "5_5") (pintype "passive"))
      (node (ref "SW3") (pin "6") (pinfunction "6_6") (pintype "passive"))
    )
    (net (code "6") (name "Net-(R8-Pad2)") (class "Default")
      (node (ref "R8") (pin "2") (pinfunction "2_2") (pintype "passive"))
      (node (ref "SW4") (pin "4") (pinfunction "4_4") (pintype "passive"))
      (node (ref "SW4") (pin "5") (pinfunction "5_5") (pintype "passive"))
      (node (ref "SW4") (pin "6") (pinfunction "6_6") (pintype "passive"))
    )
    (net (code "7") (name "Net-(R10-Pad2)") (class "Default")
      (node (ref "R10") (pin "2") (pinfunction "2_2") (pintype "passive"))
      (node (ref "SW5") (pin "4") (pinfunction "4_4") (pintype "passive"))
      (node (ref "SW5") (pin "5") (pinfunction "5_5") (pintype "passive"))
      (node (ref "SW5") (pin "6") (pinfunction "6_6") (pintype "passive"))
    )
    (net (code "8") (name "Net-(R12-Pad2)") (class "Default")
      (node (ref "R12") (pin "2") (pinfunction "2_2") (pintype "passive"))
      (node (ref "SW6") (pin "4") (pinfunction "4_4") (pintype "passive"))
      (node (ref "SW6") (pin "5") (pinfunction "5_5") (pintype "passive"))
      (node (ref "SW6") (pin "6") (pinfunction "6_6") (pintype "passive"))
    )
    (net (code "9") (name "Net-(R14-Pad2)") (class "Default")
      (node (ref "R14") (pin "2") (pinfunction "2_2") (pintype "passive"))
      (node (ref "SW7") (pin "4") (pinfunction "4_4") (pintype "passive"))
      (node (ref "SW7") (pin "5") (pinfunction "5_5") (pintype "passive"))
      (node (ref "SW7") (pin "6") (pinfunction "6_6") (pintype "passive"))
    )
    (net (code "10") (name "Net-(R16-Pad2)") (class "Default")
      (node (ref "R16") (pin "2") (pinfunction "2_2") (pintype "passive"))
      (node (ref "SW8") (pin "4") (pinfunction "4_4") (pintype "passive"))
      (node (ref "SW8") (pin "5") (pinfunction "5_5") (pintype "passive"))
      (node (ref "SW8") (pin "6") (pinfunction "6_6") (pintype "passive"))
    )
    (net (code "11") (name "Net-(R18-Pad2)") (class "Default")
      (node (ref "R18") (pin "2") (pinfunction "2_2") (pintype "passive"))
      (node (ref "SW9") (pin "4") (pinfunction "4_4") (pintype "passive"))
      (node (ref "SW9") (pin "5") (pinfunction "5_5") (pintype "passive"))
      (node (ref "SW9") (pin "6") (pinfunction "6_6") (pintype "passive"))
    )
    (net (code "12") (name "Net-(R20-Pad2)") (class "Default")
      (node (ref "R20") (pin "2") (pinfunction "2_2") (pintype "passive"))
      (node (ref "SW10") (pin "4") (pinfunction "4_4") (pintype "passive"))
      (node (ref "SW10") (pin "5") (pinfunction "5_5") (pintype "passive"))
      (node (ref "SW10") (pin "6") (pinfunction "6_6") (pintype "passive"))
    )
    (net (code "13") (name "Net-(R27-Pad2)") (class "Default")
      (node (ref "R27") (pin "2") (pinfunction "2_2") (pintype "passive"))
      (node (ref "SW11") (pin "4") (pinfunction "4_4") (pintype "passive"))
      (node (ref "SW11") (pin "5") (pinfunction "5_5") (pintype "passive"))
      (node (ref "SW11") (pin "6") (pinfunction "6_6") (pintype "passive"))
    )
    (net (code "14") (name "Net-(R29-Pad2)") (class "Default")
      (node (ref "R29") (pin "2") (pinfunction "2_2") (pintype "passive"))
      (node (ref "SW12") (pin "4") (pinfunction "4_4") (pintype "passive"))
      (node (ref "SW12") (pin "5") (pinfunction "5_5") (pintype "passive"))
      (node (ref "SW12") (pin "6") (pinfunction "6_6") (pintype "passive"))
    )
    (net (code "15") (name "Net-(R36-Pad2)") (class "Default")
      (node (ref "R36") (pin "2") (pinfunction "2_2") (pintype "passive"))
      (node (ref "SW13") (pin "4") (pinfunction "4_4") (pintype "passive"))
      (node (ref "SW13") (pin "5") (pinfunction "5_5") (pintype "passive"))
      (node (ref "SW13") (pin "6") (pinfunction "6_6") (pintype "passive"))
    )
    (net (code "16") (name "Net-(R38-Pad2)") (class "Default")
      (node (ref "R38") (pin "2") (pinfunction "2_2") (pintype "passive"))
      (node (ref "SW14") (pin "4") (pinfunction "4_4") (pintype "passive"))
      (node (ref "SW14") (pin "5") (pinfunction "5_5") (pintype "passive"))
      (node (ref "SW14") (pin "6") (pinfunction "6_6") (pintype "passive"))
    )
    (net (code "17") (name "Net-(R40-Pad2)") (class "Default")
      (node (ref "R40") (pin "2") (pinfunction "2_2") (pintype "passive"))
      (node (ref "SW15") (pin "4") (pinfunction "4_4") (pintype "passive"))
      (node (ref "SW15") (pin "5") (pinfunction "5_5") (pintype "passive"))
      (node (ref "SW15") (pin "6") (pinfunction "6_6") (pintype "passive"))
    )
    (net (code "18") (name "Net-(U$1-1)") (class "Default")
      (node (ref "U$1") (pin "P1") (pinfunction "1_P1") (pintype "bidirectional"))
      (node (ref "U1") (pin "12") (pinfunction "1A_12") (pintype "output"))
    )
    (net (code "19") (name "Net-(U$1-2)") (class "Default")
      (node (ref "U$1") (pin "P2") (pinfunction "2_P2") (pintype "bidirectional"))
      (node (ref "U1") (pin "11") (pinfunction "1B_11") (pintype "output"))
    )
    (net (code "20") (name "Net-(U$1-3)") (class "Default")
      (node (ref "U$1") (pin "P3") (pinfunction "3_P3") (pintype "bidirectional"))
      (node (ref "U1") (pin "13") (pinfunction "2A_13") (pintype "output"))
    )
    (net (code "21") (name "Net-(U$1-4)") (class "Default")
      (node (ref "U$1") (pin "P4") (pinfunction "4_P4") (pintype "bidirectional"))
      (node (ref "U1") (pin "14") (pinfunction "2B_14") (pintype "output"))
    )
    (net (code "22") (name "Net-(U$2-1)") (class "Default")
      (node (ref "U$2") (pin "P1") (pinfunction "1_P1") (pintype "bidirectional"))
      (node (ref "U2") (pin "12") (pinfunction "1A_12") (pintype "output"))
    )
    (net (code "23") (name "Net-(U$2-2)") (class "Default")
      (node (ref "U$2") (pin "P2") (pinfunction "2_P2") (pintype "bidirectional"))
      (node (ref "U2") (pin "11") (pinfunction "1B_11") (pintype "output"))
    )
    (net (code "24") (name "Net-(U$2-3)") (class "Default")
      (node (ref "U$2") (pin "P3") (pinfunction "3_P3") (pintype "bidirectional"))
      (node (ref "U2") (pin "13") (pinfunction "2A_13") (pintype "output"))
    )
    (net (code "25") (name "Net-(U$2-4)") (class "Default")
      (node (ref "U$2") (pin "P4") (pinfunction "4_P4") (pintype "bidirectional"))
      (node (ref "U2") (pin "14") (pinfunction "2B_14") (pintype "output"))
    )
    (net (code "26") (name "Net-(U$3-1)") (class "Default")
      (node (ref "U$3") (pin "P1") (pinfunction "1_P1") (pintype "bidirectional"))
      (node (ref "U3") (pin "12") (pinfunction "1A_12") (pintype "output"))
    )
    (net (code "27") (name "Net-(U$3-2)") (class "Default")
      (node (ref "U$3") (pin "P2") (pinfunction "2_P2") (pintype "bidirectional"))
      (node (ref "U3") (pin "11") (pinfunction "1B_11") (pintype "output"))
    )
    (net (code "28") (name "Net-(U$3-3)") (class "Default")
      (node (ref "U$3") (pin "P3") (pinfunction "3_P3") (pintype "bidirectional"))
      (node (ref "U3") (pin "13") (pinfunction "2A_13") (pintype "output"))
    )
    (net (code "29") (name "Net-(U$3-4)") (class "Default")
      (node (ref "U$3") (pin "P4") (pinfunction "4_P4") (pintype "bidirectional"))
      (node (ref "U3") (pin "14") (pinfunction "2B_14") (pintype "output"))
    )
    (net (code "30") (name "Net-(U$4-1)") (class "Default")
      (node (ref "U$4") (pin "P1") (pinfunction "1_P1") (pintype "bidirectional"))
      (node (ref "U4") (pin "12") (pinfunction "1A_12") (pintype "output"))
    )
    (net (code "31") (name "Net-(U$4-2)") (class "Default")
      (node (ref "U$4") (pin "P2") (pinfunction "2_P2") (pintype "bidirectional"))
      (node (ref "U4") (pin "11") (pinfunction "1B_11") (pintype "output"))
    )
    (net (code "32") (name "Net-(U$4-3)") (class "Default")
      (node (ref "U$4") (pin "P3") (pinfunction "3_P3") (pintype "bidirectional"))
      (node (ref "U4") (pin "13") (pinfunction "2A_13") (pintype "output"))
    )
    (net (code "33") (name "Net-(U$4-4)") (class "Default")
      (node (ref "U$4") (pin "P4") (pinfunction "4_P4") (pintype "bidirectional"))
      (node (ref "U4") (pin "14") (pinfunction "2B_14") (pintype "output"))
    )
    (net (code "34") (name "Net-(U$5-1)") (class "Default")
      (node (ref "U$5") (pin "P1") (pinfunction "1_P1") (pintype "bidirectional"))
      (node (ref "U5") (pin "12") (pinfunction "1A_12") (pintype "output"))
    )
    (net (code "35") (name "Net-(U$5-2)") (class "Default")
      (node (ref "U$5") (pin "P2") (pinfunction "2_P2") (pintype "bidirectional"))
      (node (ref "U5") (pin "11") (pinfunction "1B_11") (pintype "output"))
    )
    (net (code "36") (name "Net-(U$5-3)") (class "Default")
      (node (ref "U$5") (pin "P3") (pinfunction "3_P3") (pintype "bidirectional"))
      (node (ref "U5") (pin "13") (pinfunction "2A_13") (pintype "output"))
    )
    (net (code "37") (name "Net-(U$5-4)") (class "Default")
      (node (ref "U$5") (pin "P4") (pinfunction "4_P4") (pintype "bidirectional"))
      (node (ref "U5") (pin "14") (pinfunction "2B_14") (pintype "output"))
    )
    (net (code "38") (name "Net-(U$6-1)") (class "Default")
      (node (ref "U$6") (pin "P1") (pinfunction "1_P1") (pintype "bidirectional"))
      (node (ref "U6") (pin "12") (pinfunction "1A_12") (pintype "output"))
    )
    (net (code "39") (name "Net-(U$6-2)") (class "Default")
      (node (ref "U$6") (pin "P2") (pinfunction "2_P2") (pintype "bidirectional"))
      (node (ref "U6") (pin "11") (pinfunction "1B_11") (pintype "output"))
    )
    (net (code "40") (name "Net-(U$6-3)") (class "Default")
      (node (ref "U$6") (pin "P3") (pinfunction "3_P3") (pintype "bidirectional"))
      (node (ref "U6") (pin "13") (pinfunction "2A_13") (pintype "output"))
    )
    (net (code "41") (name "Net-(U$6-4)") (class "Default")
      (node (ref "U$6") (pin "P4") (pinfunction "4_P4") (pintype "bidirectional"))
      (node (ref "U6") (pin "14") (pinfunction "2B_14") (pintype "output"))
    )
    (net (code "42") (name "Net-(U$7-1)") (class "Default")
      (node (ref "U$7") (pin "P1") (pinfunction "1_P1") (pintype "bidirectional"))
      (node (ref "U7") (pin "12") (pinfunction "1A_12") (pintype "output"))
    )
    (net (code "43") (name "Net-(U$7-2)") (class "Default")
      (node (ref "U$7") (pin "P2") (pinfunction "2_P2") (pintype "bidirectional"))
      (node (ref "U7") (pin "11") (pinfunction "1B_11") (pintype "output"))
    )
    (net (code "44") (name "Net-(U$7-3)") (class "Default")
      (node (ref "U$7") (pin "P3") (pinfunction "3_P3") (pintype "bidirectional"))
      (node (ref "U7") (pin "13") (pinfunction "2A_13") (pintype "output"))
    )
    (net (code "45") (name "Net-(U$7-4)") (class "Default")
      (node (ref "U$7") (pin "P4") (pinfunction "4_P4") (pintype "bidirectional"))
      (node (ref "U7") (pin "14") (pinfunction "2B_14") (pintype "output"))
    )
    (net (code "46") (name "Net-(U$8-1)") (class "Default")
      (node (ref "U$8") (pin "P1") (pinfunction "1_P1") (pintype "bidirectional"))
      (node (ref "U8") (pin "12") (pinfunction "1A_12") (pintype "output"))
    )
    (net (code "47") (name "Net-(U$8-2)") (class "Default")
      (node (ref "U$8") (pin "P2") (pinfunction "2_P2") (pintype "bidirectional"))
      (node (ref "U8") (pin "11") (pinfunction "1B_11") (pintype "output"))
    )
    (net (code "48") (name "Net-(U$8-3)") (class "Default")
      (node (ref "U$8") (pin "P3") (pinfunction "3_P3") (pintype "bidirectional"))
      (node (ref "U8") (pin "13") (pinfunction "2A_13") (pintype "output"))
    )
    (net (code "49") (name "Net-(U$8-4)") (class "Default")
      (node (ref "U$8") (pin "P4") (pinfunction "4_P4") (pintype "bidirectional"))
      (node (ref "U8") (pin "14") (pinfunction "2B_14") (pintype "output"))
    )
    (net (code "50") (name "Net-(U$9-1)") (class "Default")
      (node (ref "U$9") (pin "P1") (pinfunction "1_P1") (pintype "bidirectional"))
      (node (ref "U9") (pin "12") (pinfunction "1A_12") (pintype "output"))
    )
    (net (code "51") (name "Net-(U$9-2)") (class "Default")
      (node (ref "U$9") (pin "P2") (pinfunction "2_P2") (pintype "bidirectional"))
      (node (ref "U9") (pin "11") (pinfunction "1B_11") (pintype "output"))
    )
    (net (code "52") (name "Net-(U$9-3)") (class "Default")
      (node (ref "U$9") (pin "P3") (pinfunction "3_P3") (pintype "bidirectional"))
      (node (ref "U9") (pin "13") (pinfunction "2A_13") (pintype "output"))
    )
    (net (code "53") (name "Net-(U$9-4)") (class "Default")
      (node (ref "U$9") (pin "P4") (pinfunction "4_P4") (pintype "bidirectional"))
      (node (ref "U9") (pin "14") (pinfunction "2B_14") (pintype "output"))
    )
    (net (code "54") (name "Net-(U$10-1)") (class "Default")
      (node (ref "U$10") (pin "P1") (pinfunction "1_P1") (pintype "bidirectional"))
      (node (ref "U10") (pin "12") (pinfunction "1A_12") (pintype "output"))
    )
    (net (code "55") (name "Net-(U$10-2)") (class "Default")
      (node (ref "U$10") (pin "P2") (pinfunction "2_P2") (pintype "bidirectional"))
      (node (ref "U10") (pin "11") (pinfunction "1B_11") (pintype "output"))
    )
    (net (code "56") (name "Net-(U$10-3)") (class "Default")
      (node (ref "U$10") (pin "P3") (pinfunction "3_P3") (pintype "bidirectional"))
      (node (ref "U10") (pin "13") (pinfunction "2A_13") (pintype "output"))
    )
    (net (code "57") (name "Net-(U$10-4)") (class "Default")
      (node (ref "U$10") (pin "P4") (pinfunction "4_P4") (pintype "bidirectional"))
      (node (ref "U10") (pin "14") (pinfunction "2B_14") (pintype "output"))
    )
    (net (code "58") (name "Net-(U$11-1)") (class "Default")
      (node (ref "U$11") (pin "P1") (pinfunction "1_P1") (pintype "bidirectional"))
      (node (ref "U11") (pin "12") (pinfunction "1A_12") (pintype "output"))
    )
    (net (code "59") (name "Net-(U$11-2)") (class "Default")
      (node (ref "U$11") (pin "P2") (pinfunction "2_P2") (pintype "bidirectional"))
      (node (ref "U11") (pin "11") (pinfunction "1B_11") (pintype "output"))
    )
    (net (code "60") (name "Net-(U$11-3)") (class "Default")
      (node (ref "U$11") (pin "P3") (pinfunction "3_P3") (pintype "bidirectional"))
      (node (ref "U11") (pin "13") (pinfunction "2A_13") (pintype "output"))
    )
    (net (code "61") (name "Net-(U$11-4)") (class "Default")
      (node (ref "U$11") (pin "P4") (pinfunction "4_P4") (pintype "bidirectional"))
      (node (ref "U11") (pin "14") (pinfunction "2B_14") (pintype "output"))
    )
    (net (code "62") (name "Net-(U$12-1)") (class "Default")
      (node (ref "U$12") (pin "P1") (pinfunction "1_P1") (pintype "bidirectional"))
      (node (ref "U12") (pin "12") (pinfunction "1A_12") (pintype "output"))
    )
    (net (code "63") (name "Net-(U$12-2)") (class "Default")
      (node (ref "U$12") (pin "P2") (pinfunction "2_P2") (pintype "bidirectional"))
      (node (ref "U12") (pin "11") (pinfunction "1B_11") (pintype "output"))
    )
    (net (code "64") (name "Net-(U$12-3)") (class "Default")
      (node (ref "U$12") (pin "P3") (pinfunction "3_P3") (pintype "bidirectional"))
      (node (ref "U12") (pin "13") (pinfunction "2A_13") (pintype "output"))
    )
    (net (code "65") (name "Net-(U$12-4)") (class "Default")
      (node (ref "U$12") (pin "P4") (pinfunction "4_P4") (pintype "bidirectional"))
      (node (ref "U12") (pin "14") (pinfunction "2B_14") (pintype "output"))
    )
    (net (code "66") (name "Net-(U$13-1)") (class "Default")
      (node (ref "U$13") (pin "P1") (pinfunction "1_P1") (pintype "bidirectional"))
      (node (ref "U13") (pin "12") (pinfunction "1A_12") (pintype "output"))
    )
    (net (code "67") (name "Net-(U$13-2)") (class "Default")
      (node (ref "U$13") (pin "P2") (pinfunction "2_P2") (pintype "bidirectional"))
      (node (ref "U13") (pin "11") (pinfunction "1B_11") (pintype "output"))
    )
    (net (code "68") (name "Net-(U$13-3)") (class "Default")
      (node (ref "U$13") (pin "P3") (pinfunction "3_P3") (pintype "bidirectional"))
      (node (ref "U13") (pin "13") (pinfunction "2A_13") (pintype "output"))
    )
    (net (code "69") (name "Net-(U$13-4)") (class "Default")
      (node (ref "U$13") (pin "P4") (pinfunction "4_P4") (pintype "bidirectional"))
      (node (ref "U13") (pin "14") (pinfunction "2B_14") (pintype "output"))
    )
    (net (code "70") (name "Net-(U$14-1)") (class "Default")
      (node (ref "U$14") (pin "P1") (pinfunction "1_P1") (pintype "bidirectional"))
      (node (ref "U14") (pin "12") (pinfunction "1A_12") (pintype "output"))
    )
    (net (code "71") (name "Net-(U$14-2)") (class "Default")
      (node (ref "U$14") (pin "P2") (pinfunction "2_P2") (pintype "bidirectional"))
      (node (ref "U14") (pin "11") (pinfunction "1B_11") (pintype "output"))
    )
    (net (code "72") (name "Net-(U$14-3)") (class "Default")
      (node (ref "U$14") (pin "P3") (pinfunction "3_P3") (pintype "bidirectional"))
      (node (ref "U14") (pin "13") (pinfunction "2A_13") (pintype "output"))
    )
    (net (code "73") (name "Net-(U$14-4)") (class "Default")
      (node (ref "U$14") (pin "P4") (pinfunction "4_P4") (pintype "bidirectional"))
      (node (ref "U14") (pin "14") (pinfunction "2B_14") (pintype "output"))
    )
    (net (code "74") (name "Net-(U$15-1)") (class "Default")
      (node (ref "U$15") (pin "P1") (pinfunction "1_P1") (pintype "bidirectional"))
      (node (ref "U15") (pin "12") (pinfunction "1A_12") (pintype "output"))
    )
    (net (code "75") (name "Net-(U$15-2)") (class "Default")
      (node (ref "U$15") (pin "P2") (pinfunction "2_P2") (pintype "bidirectional"))
      (node (ref "U15") (pin "11") (pinfunction "1B_11") (pintype "output"))
    )
    (net (code "76") (name "Net-(U$15-3)") (class "Default")
      (node (ref "U$15") (pin "P3") (pinfunction "3_P3") (pintype "bidirectional"))
      (node (ref "U15") (pin "13") (pinfunction "2A_13") (pintype "output"))
    )
    (net (code "77") (name "Net-(U$15-4)") (class "Default")
      (node (ref "U$15") (pin "P4") (pinfunction "4_P4") (pintype "bidirectional"))
      (node (ref "U15") (pin "14") (pinfunction "2B_14") (pintype "output"))
    )
    (net (code "78") (name "Net-(U1-DIR)") (class "Default")
      (node (ref "J1") (pin "29") (pinfunction "29_29") (pintype "passive"))
      (node (ref "U1") (pin "8") (pinfunction "DIR_8") (pintype "input"))
    )
    (net (code "79") (name "Net-(U1-MS1)") (class "Default")
      (node (ref "SW1") (pin "1") (pinfunction "1_1") (pintype "passive"))
      (node (ref "U1") (pin "2") (pinfunction "MS1_2") (pintype "input"))
    )
    (net (code "80") (name "Net-(U1-MS2)") (class "Default")
      (node (ref "SW1") (pin "2") (pinfunction "2_2") (pintype "passive"))
      (node (ref "U1") (pin "3") (pinfunction "MS2_3") (pintype "input"))
    )
    (net (code "81") (name "Net-(U1-MS3)") (class "Default")
      (node (ref "SW1") (pin "3") (pinfunction "3_3") (pintype "passive"))
      (node (ref "U1") (pin "4") (pinfunction "MS3_4") (pintype "input"))
    )
    (net (code "82") (name "Net-(U1-STEP)") (class "Default")
      (node (ref "J1") (pin "31") (pinfunction "31_31") (pintype "passive"))
      (node (ref "U1") (pin "7") (pinfunction "STEP_7") (pintype "input"))
    )
    (net (code "83") (name "Net-(U1-VDD)") (class "Default")
      (node (ref "JP2") (pin "5") (pinfunction "5_5") (pintype "passive"))
      (node (ref "R10") (pin "1") (pinfunction "1_1") (pintype "passive"))
      (node (ref "R12") (pin "1") (pinfunction "1_1") (pintype "passive"))
      (node (ref "R14") (pin "1") (pinfunction "1_1") (pintype "passive"))
      (node (ref "R16") (pin "1") (pinfunction "1_1") (pintype "passive"))
      (node (ref "R18") (pin "1") (pinfunction "1_1") (pintype "passive"))
      (node (ref "R2") (pin "1") (pinfunction "1_1") (pintype "passive"))
      (node (ref "R20") (pin "1") (pinfunction "1_1") (pintype "passive"))
      (node (ref "R27") (pin "1") (pinfunction "1_1") (pintype "passive"))
      (node (ref "R29") (pin "1") (pinfunction "1_1") (pintype "passive"))
      (node (ref "R36") (pin "1") (pinfunction "1_1") (pintype "passive"))
      (node (ref "R38") (pin "1") (pinfunction "1_1") (pintype "passive"))
      (node (ref "R4") (pin "1") (pinfunction "1_1") (pintype "passive"))
      (node (ref "R40") (pin "1") (pinfunction "1_1") (pintype "passive"))
      (node (ref "R6") (pin "1") (pinfunction "1_1") (pintype "passive"))
      (node (ref "R8") (pin "1") (pinfunction "1_1") (pintype "passive"))
      (node (ref "U1") (pin "10") (pinfunction "VDD_10") (pintype "power_in"))
      (node (ref "U10") (pin "10") (pinfunction "VDD_10") (pintype "power_in"))
      (node (ref "U11") (pin "10") (pinfunction "VDD_10") (pintype "power_in"))
      (node (ref "U12") (pin "10") (pinfunction "VDD_10") (pintype "power_in"))
      (node (ref "U13") (pin "10") (pinfunction "VDD_10") (pintype "power_in"))
      (node (ref "U14") (pin "10") (pinfunction "VDD_10") (pintype "power_in"))
      (node (ref "U15") (pin "10") (pinfunction "VDD_10") (pintype "power_in"))
      (node (ref "U2") (pin "10") (pinfunction "VDD_10") (pintype "power_in"))
      (node (ref "U3") (pin "10") (pinfunction "VDD_10") (pintype "power_in"))
      (node (ref "U4") (pin "10") (pinfunction "VDD_10") (pintype "power_in"))
      (node (ref "U5") (pin "10") (pinfunction "VDD_10") (pintype "power_in"))
      (node (ref "U6") (pin "10") (pinfunction "VDD_10") (pintype "power_in"))
      (node (ref "U7") (pin "10") (pinfunction "VDD_10") (pintype "power_in"))
      (node (ref "U8") (pin "10") (pinfunction "VDD_10") (pintype "power_in"))
      (node (ref "U9") (pin "10") (pinfunction "VDD_10") (pintype "power_in"))
      (node (ref "X2") (pin "2") (pinfunction "KL_2") (pintype "passive"))
    )
    (net (code "84") (name "Net-(U1-~{ENABLE})") (class "Default")
      (node (ref "JP5") (pin "1") (pinfunction "1_1") (pintype "passive"))
      (node (ref "R21") (pin "2") (pinfunction "2_2") (pintype "passive"))
      (node (ref "U1") (pin "1") (pinfunction "~{ENABLE}_1") (pintype "input"))
    )
    (net (code "85") (name "Net-(U1-~{RESET})") (class "Default")
      (node (ref "J1") (pin "33") (pinfunction "33_33") (pintype "passive"))
      (node (ref "U1") (pin "5") (pinfunction "~{RESET}_5") (pintype "input"))
      (node (ref "U1") (pin "6") (pinfunction "~{SLEEP}_6") (pintype "input"))
    )
    (net (code "86") (name "Net-(U2-DIR)") (class "Default")
      (node (ref "J1") (pin "23") (pinfunction "23_23") (pintype "passive"))
      (node (ref "U2") (pin "8") (pinfunction "DIR_8") (pintype "input"))
    )
    (net (code "87") (name "Net-(U2-MS1)") (class "Default")
      (node (ref "SW2") (pin "1") (pinfunction "1_1") (pintype "passive"))
      (node (ref "U2") (pin "2") (pinfunction "MS1_2") (pintype "input"))
    )
    (net (code "88") (name "Net-(U2-MS2)") (class "Default")
      (node (ref "SW2") (pin "2") (pinfunction "2_2") (pintype "passive"))
      (node (ref "U2") (pin "3") (pinfunction "MS2_3") (pintype "input"))
    )
    (net (code "89") (name "Net-(U2-MS3)") (class "Default")
      (node (ref "SW2") (pin "3") (pinfunction "3_3") (pintype "passive"))
      (node (ref "U2") (pin "4") (pinfunction "MS3_4") (pintype "input"))
    )
    (net (code "90") (name "Net-(U2-STEP)") (class "Default")
      (node (ref "J1") (pin "25") (pinfunction "25_25") (pintype "passive"))
      (node (ref "U2") (pin "7") (pinfunction "STEP_7") (pintype "input"))
    )
    (net (code "91") (name "Net-(U2-~{ENABLE})") (class "Default")
      (node (ref "JP6") (pin "1") (pinfunction "1_1") (pintype "passive"))
      (node (ref "R22") (pin "2") (pinfunction "2_2") (pintype "passive"))
      (node (ref "U2") (pin "1") (pinfunction "~{ENABLE}_1") (pintype "input"))
    )
    (net (code "92") (name "Net-(U2-~{RESET})") (class "Default")
      (node (ref "J1") (pin "27") (pinfunction "27_27") (pintype "passive"))
      (node (ref "U2") (pin "5") (pinfunction "~{RESET}_5") (pintype "input"))
      (node (ref "U2") (pin "6") (pinfunction "~{SLEEP}_6") (pintype "input"))
    )
    (net (code "93") (name "Net-(U3-DIR)") (class "Default")
      (node (ref "J1") (pin "17") (pinfunction "17_17") (pintype "passive"))
      (node (ref "U3") (pin "8") (pinfunction "DIR_8") (pintype "input"))
    )
    (net (code "94") (name "Net-(U3-MS1)") (class "Default")
      (node (ref "SW3") (pin "1") (pinfunction "1_1") (pintype "passive"))
      (node (ref "U3") (pin "2") (pinfunction "MS1_2") (pintype "input"))
    )
    (net (code "95") (name "Net-(U3-MS2)") (class "Default")
      (node (ref "SW3") (pin "2") (pinfunction "2_2") (pintype "passive"))
      (node (ref "U3") (pin "3") (pinfunction "MS2_3") (pintype "input"))
    )
    (net (code "96") (name "Net-(U3-MS3)") (class "Default")
      (node (ref "SW3") (pin "3") (pinfunction "3_3") (pintype "passive"))
      (node (ref "U3") (pin "4") (pinfunction "MS3_4") (pintype "input"))
    )
    (net (code "97") (name "Net-(U3-STEP)") (class "Default")
      (node (ref "J1") (pin "19") (pinfunction "19_19") (pintype "passive"))
      (node (ref "U3") (pin "7") (pinfunction "STEP_7") (pintype "input"))
    )
    (net (code "98") (name "Net-(U3-~{ENABLE})") (class "Default")
      (node (ref "JP7") (pin "1") (pinfunction "1_1") (pintype "passive"))
      (node (ref "R23") (pin "2") (pinfunction "2_2") (pintype "passive"))
      (node (ref "U3") (pin "1") (pinfunction "~{ENABLE}_1") (pintype "input"))
    )
    (net (code "99") (name "Net-(U3-~{RESET})") (class "Default")
      (node (ref "J1") (pin "21") (pinfunction "21_21") (pintype "passive"))
      (node (ref "U3") (pin "5") (pinfunction "~{RESET}_5") (pintype "input"))
      (node (ref "U3") (pin "6") (pinfunction "~{SLEEP}_6") (pintype "input"))
    )
    (net (code "100") (name "Net-(U4-DIR)") (class "Default")
      (node (ref "J1") (pin "11") (pinfunction "11_11") (pintype "passive"))
      (node (ref "U4") (pin "8") (pinfunction "DIR_8") (pintype "input"))
    )
    (net (code "101") (name "Net-(U4-MS1)") (class "Default")
      (node (ref "SW4") (pin "1") (pinfunction "1_1") (pintype "passive"))
      (node (ref "U4") (pin "2") (pinfunction "MS1_2") (pintype "input"))
    )
    (net (code "102") (name "Net-(U4-MS2)") (class "Default")
      (node (ref "SW4") (pin "2") (pinfunction "2_2") (pintype "passive"))
      (node (ref "U4") (pin "3") (pinfunction "MS2_3") (pintype "input"))
    )
    (net (code "103") (name "Net-(U4-MS3)") (class "Default")
      (node (ref "SW4") (pin "3") (pinfunction "3_3") (pintype "passive"))
      (node (ref "U4") (pin "4") (pinfunction "MS3_4") (pintype "input"))
    )
    (net (code "104") (name "Net-(U4-STEP)") (class "Default")
      (node (ref "J1") (pin "13") (pinfunction "13_13") (pintype "passive"))
      (node (ref "U4") (pin "7") (pinfunction "STEP_7") (pintype "input"))
    )
    (net (code "105") (name "Net-(U4-~{ENABLE})") (class "Default")
      (node (ref "JP8") (pin "1") (pinfunction "1_1") (pintype "passive"))
      (node (ref "R24") (pin "2") (pinfunction "2_2") (pintype "passive"))
      (node (ref "U4") (pin "1") (pinfunction "~{ENABLE}_1") (pintype "input"))
    )
    (net (code "106") (name "Net-(U4-~{RESET})") (class "Default")
      (node (ref "J1") (pin "15") (pinfunction "15_15") (pintype "passive"))
      (node (ref "U4") (pin "5") (pinfunction "~{RESET}_5") (pintype "input"))
      (node (ref "U4") (pin "6") (pinfunction "~{SLEEP}_6") (pintype "input"))
    )
    (net (code "107") (name "Net-(U5-DIR)") (class "Default")
      (node (ref "J1") (pin "5") (pinfunction "5_5") (pintype "passive"))
      (node (ref "U5") (pin "8") (pinfunction "DIR_8") (pintype "input"))
    )
    (net (code "108") (name "Net-(U5-MS1)") (class "Default")
      (node (ref "SW5") (pin "1") (pinfunction "1_1") (pintype "passive"))
      (node (ref "U5") (pin "2") (pinfunction "MS1_2") (pintype "input"))
    )
    (net (code "109") (name "Net-(U5-MS2)") (class "Default")
      (node (ref "SW5") (pin "2") (pinfunction "2_2") (pintype "passive"))
      (node (ref "U5") (pin "3") (pinfunction "MS2_3") (pintype "input"))
    )
    (net (code "110") (name "Net-(U5-MS3)") (class "Default")
      (node (ref "SW5") (pin "3") (pinfunction "3_3") (pintype "passive"))
      (node (ref "U5") (pin "4") (pinfunction "MS3_4") (pintype "input"))
    )
    (net (code "111") (name "Net-(U5-STEP)") (class "Default")
      (node (ref "J1") (pin "7") (pinfunction "7_7") (pintype "passive"))
      (node (ref "U5") (pin "7") (pinfunction "STEP_7") (pintype "input"))
    )
    (net (code "112") (name "Net-(U5-~{ENABLE})") (class "Default")
      (node (ref "JP9") (pin "1") (pinfunction "1_1") (pintype "passive"))
      (node (ref "R25") (pin "2") (pinfunction "2_2") (pintype "passive"))
      (node (ref "U5") (pin "1") (pinfunction "~{ENABLE}_1") (pintype "input"))
    )
    (net (code "113") (name "Net-(U5-~{RESET})") (class "Default")
      (node (ref "J1") (pin "9") (pinfunction "9_9") (pintype "passive"))
      (node (ref "U5") (pin "5") (pinfunction "~{RESET}_5") (pintype "input"))
      (node (ref "U5") (pin "6") (pinfunction "~{SLEEP}_6") (pintype "input"))
    )
    (net (code "114") (name "Net-(U6-DIR)") (class "Default")
      (node (ref "J1") (pin "10") (pinfunction "10_10") (pintype "passive"))
      (node (ref "U6") (pin "8") (pinfunction "DIR_8") (pintype "input"))
    )
    (net (code "115") (name "Net-(U6-MS1)") (class "Default")
      (node (ref "SW6") (pin "1") (pinfunction "1_1") (pintype "passive"))
      (node (ref "U6") (pin "2") (pinfunction "MS1_2") (pintype "input"))
    )
    (net (code "116") (name "Net-(U6-MS2)") (class "Default")
      (node (ref "SW6") (pin "2") (pinfunction "2_2") (pintype "passive"))
      (node (ref "U6") (pin "3") (pinfunction "MS2_3") (pintype "input"))
    )
    (net (code "117") (name "Net-(U6-MS3)") (class "Default")
      (node (ref "SW6") (pin "3") (pinfunction "3_3") (pintype "passive"))
      (node (ref "U6") (pin "4") (pinfunction "MS3_4") (pintype "input"))
    )
    (net (code "118") (name "Net-(U6-STEP)") (class "Default")
      (node (ref "J1") (pin "8") (pinfunction "8_8") (pintype "passive"))
      (node (ref "U6") (pin "7") (pinfunction "STEP_7") (pintype "input"))
    )
    (net (code "119") (name "Net-(U6-~{ENABLE})") (class "Default")
      (node (ref "JP10") (pin "1") (pinfunction "1_1") (pintype "passive"))
      (node (ref "R31") (pin "2") (pinfunction "2_2") (pintype "passive"))
      (node (ref "U6") (pin "1") (pinfunction "~{ENABLE}_1") (pintype "input"))
    )
    (net (code "120") (name "Net-(U6-~{RESET})") (class "Default")
      (node (ref "J1") (pin "6") (pinfunction "6_6") (pintype "passive"))
      (node (ref "U6") (pin "5") (pinfunction "~{RESET}_5") (pintype "input"))
      (node (ref "U6") (pin "6") (pinfunction "~{SLEEP}_6") (pintype "input"))
    )
    (net (code "121") (name "Net-(U7-DIR)") (class "Default")
      (node (ref "J1") (pin "16") (pinfunction "16_16") (pintype "passive"))
      (node (ref "U7") (pin "8") (pinfunction "DIR_8") (pintype "input"))
    )
    (net (code "122") (name "Net-(U7-MS1)") (class "Default")
      (node (ref "SW7") (pin "1") (pinfunction "1_1") (pintype "passive"))
      (node (ref "U7") (pin "2") (pinfunction "MS1_2") (pintype "input"))
    )
    (net (code "123") (name "Net-(U7-MS2)") (class "Default")
      (node (ref "SW7") (pin "2") (pinfunction "2_2") (pintype "passive"))
      (node (ref "U7") (pin "3") (pinfunction "MS2_3") (pintype "input"))
    )
    (net (code "124") (name "Net-(U7-MS3)") (class "Default")
      (node (ref "SW7") (pin "3") (pinfunction "3_3") (pintype "passive"))
      (node (ref "U7") (pin "4") (pinfunction "MS3_4") (pintype "input"))
    )
    (net (code "125") (name "Net-(U7-STEP)") (class "Default")
      (node (ref "J1") (pin "14") (pinfunction "14_14") (pintype "passive"))
      (node (ref "U7") (pin "7") (pinfunction "STEP_7") (pintype "input"))
    )
    (net (code "126") (name "Net-(U7-~{ENABLE})") (class "Default")
      (node (ref "JP11") (pin "1") (pinfunction "1_1") (pintype "passive"))
      (node (ref "R32") (pin "2") (pinfunction "2_2") (pintype "passive"))
      (node (ref "U7") (pin "1") (pinfunction "~{ENABLE}_1") (pintype "input"))
    )
    (net (code "127") (name "Net-(U7-~{RESET})") (class "Default")
      (node (ref "J1") (pin "12") (pinfunction "12_12") (pintype "passive"))
      (node (ref "U7") (pin "5") (pinfunction "~{RESET}_5") (pintype "input"))
      (node (ref "U7") (pin "6") (pinfunction "~{SLEEP}_6") (pintype "input"))
    )
    (net (code "128") (name "Net-(U8-DIR)") (class "Default")
      (node (ref "J1") (pin "22") (pinfunction "22_22") (pintype "passive"))
      (node (ref "U8") (pin "8") (pinfunction "DIR_8") (pintype "input"))
    )
    (net (code "129") (name "Net-(U8-MS1)") (class "Default")
      (node (ref "SW8") (pin "1") (pinfunction "1_1") (pintype "passive"))
      (node (ref "U8") (pin "2") (pinfunction "MS1_2") (pintype "input"))
    )
    (net (code "130") (name "Net-(U8-MS2)") (class "Default")
      (node (ref "SW8") (pin "2") (pinfunction "2_2") (pintype "passive"))
      (node (ref "U8") (pin "3") (pinfunction "MS2_3") (pintype "input"))
    )
    (net (code "131") (name "Net-(U8-MS3)") (class "Default")
      (node (ref "SW8") (pin "3") (pinfunction "3_3") (pintype "passive"))
      (node (ref "U8") (pin "4") (pinfunction "MS3_4") (pintype "input"))
    )
    (net (code "132") (name "Net-(U8-STEP)") (class "Default")
      (node (ref "J1") (pin "20") (pinfunction "20_20") (pintype "passive"))
      (node (ref "U8") (pin "7") (pinfunction "STEP_7") (pintype "input"))
    )
    (net (code "133") (name "Net-(U8-~{ENABLE})") (class "Default")
      (node (ref "JP12") (pin "1") (pinfunction "1_1") (pintype "passive"))
      (node (ref "R33") (pin "2") (pinfunction "2_2") (pintype "passive"))
      (node (ref "U8") (pin "1") (pinfunction "~{ENABLE}_1") (pintype "input"))
    )
    (net (code "134") (name "Net-(U8-~{RESET})") (class "Default")
      (node (ref "J1") (pin "18") (pinfunction "18_18") (pintype "passive"))
      (node (ref "U8") (pin "5") (pinfunction "~{RESET}_5") (pintype "input"))
      (node (ref "U8") (pin "6") (pinfunction "~{SLEEP}_6") (pintype "input"))
    )
    (net (code "135") (name "Net-(U9-DIR)") (class "Default")
      (node (ref "J1") (pin "28") (pinfunction "28_28") (pintype "passive"))
      (node (ref "U9") (pin "8") (pinfunction "DIR_8") (pintype "input"))
    )
    (net (code "136") (name "Net-(U9-MS1)") (class "Default")
      (node (ref "SW9") (pin "1") (pinfunction "1_1") (pintype "passive"))
      (node (ref "U9") (pin "2") (pinfunction "MS1_2") (pintype "input"))
    )
    (net (code "137") (name "Net-(U9-MS2)") (class "Default")
      (node (ref "SW9") (pin "2") (pinfunction "2_2") (pintype "passive"))
      (node (ref "U9") (pin "3") (pinfunction "MS2_3") (pintype "input"))
    )
    (net (code "138") (name "Net-(U9-MS3)") (class "Default")
      (node (ref "SW9") (pin "3") (pinfunction "3_3") (pintype "passive"))
      (node (ref "U9") (pin "4") (pinfunction "MS3_4") (pintype "input"))
    )
    (net (code "139") (name "Net-(U9-STEP)") (class "Default")
      (node (ref "J1") (pin "26") (pinfunction "26_26") (pintype "passive"))
      (node (ref "U9") (pin "7") (pinfunction "STEP_7") (pintype "input"))
    )
    (net (code "140") (name "Net-(U9-~{ENABLE})") (class "Default")
      (node (ref "JP13") (pin "1") (pinfunction "1_1") (pintype "passive"))
      (node (ref "R34") (pin "2") (pinfunction "2_2") (pintype "passive"))
      (node (ref "U9") (pin "1") (pinfunction "~{ENABLE}_1") (pintype "input"))
    )
    (net (code "141") (name "Net-(U9-~{RESET})") (class "Default")
      (node (ref "J1") (pin "24") (pinfunction "24_24") (pintype "passive"))
      (node (ref "U9") (pin "5") (pinfunction "~{RESET}_5") (pintype "input"))
      (node (ref "U9") (pin "6") (pinfunction "~{SLEEP}_6") (pintype "input"))
    )
    (net (code "142") (name "Net-(U10-DIR)") (class "Default")
      (node (ref "J1") (pin "34") (pinfunction "34_34") (pintype "passive"))
      (node (ref "U10") (pin "8") (pinfunction "DIR_8") (pintype "input"))
    )
    (net (code "143") (name "Net-(U10-MS1)") (class "Default")
      (node (ref "SW10") (pin "1") (pinfunction "1_1") (pintype "passive"))
      (node (ref "U10") (pin "2") (pinfunction "MS1_2") (pintype "input"))
    )
    (net (code "144") (name "Net-(U10-MS2)") (class "Default")
      (node (ref "SW10") (pin "2") (pinfunction "2_2") (pintype "passive"))
      (node (ref "U10") (pin "3") (pinfunction "MS2_3") (pintype "input"))
    )
    (net (code "145") (name "Net-(U10-MS3)") (class "Default")
      (node (ref "SW10") (pin "3") (pinfunction "3_3") (pintype "passive"))
      (node (ref "U10") (pin "4") (pinfunction "MS3_4") (pintype "input"))
    )
    (net (code "146") (name "Net-(U10-STEP)") (class "Default")
      (node (ref "J1") (pin "32") (pinfunction "32_32") (pintype "passive"))
      (node (ref "U10") (pin "7") (pinfunction "STEP_7") (pintype "input"))
    )
    (net (code "147") (name "Net-(U10-~{ENABLE})") (class "Default")
      (node (ref "JP14") (pin "1") (pinfunction "1_1") (pintype "passive"))
      (node (ref "R35") (pin "2") (pinfunction "2_2") (pintype "passive"))
      (node (ref "U10") (pin "1") (pinfunction "~{ENABLE}_1") (pintype "input"))
    )
    (net (code "148") (name "Net-(U10-~{RESET})") (class "Default")
      (node (ref "J1") (pin "30") (pinfunction "30_30") (pintype "passive"))
      (node (ref "U10") (pin "5") (pinfunction "~{RESET}_5") (pintype "input"))
      (node (ref "U10") (pin "6") (pinfunction "~{SLEEP}_6") (pintype "input"))
    )
    (net (code "149") (name "Net-(U11-DIR)") (class "Default")
      (node (ref "JP16") (pin "5") (pinfunction "5_5") (pintype "passive"))
      (node (ref "U11") (pin "8") (pinfunction "DIR_8") (pintype "input"))
    )
    (net (code "150") (name "Net-(U11-MS1)") (class "Default")
      (node (ref "SW11") (pin "1") (pinfunction "1_1") (pintype "passive"))
      (node (ref "U11") (pin "2") (pinfunction "MS1_2") (pintype "input"))
    )
    (net (code "151") (name "Net-(U11-MS2)") (class "Default")
      (node (ref "SW11") (pin "2") (pinfunction "2_2") (pintype "passive"))
      (node (ref "U11") (pin "3") (pinfunction "MS2_3") (pintype "input"))
    )
    (net (code "152") (name "Net-(U11-MS3)") (class "Default")
      (node (ref "SW11") (pin "3") (pinfunction "3_3") (pintype "passive"))
      (node (ref "U11") (pin "4") (pinfunction "MS3_4") (pintype "input"))
    )
    (net (code "153") (name "Net-(U11-STEP)") (class "Default")
      (node (ref "JP16") (pin "6") (pinfunction "6_6") (pintype "passive"))
      (node (ref "U11") (pin "7") (pinfunction "STEP_7") (pintype "input"))
    )
    (net (code "154") (name "Net-(U11-~{ENABLE})") (class "Default")
      (node (ref "JP15") (pin "1") (pinfunction "1_1") (pintype "passive"))
      (node (ref "R41") (pin "2") (pinfunction "2_2") (pintype "passive"))
      (node (ref "U11") (pin "1") (pinfunction "~{ENABLE}_1") (pintype "input"))
    )
    (net (code "155") (name "Net-(U11-~{RESET})") (class "Default")
      (node (ref "JP16") (pin "7") (pinfunction "7_7") (pintype "passive"))
      (node (ref "U11") (pin "5") (pinfunction "~{RESET}_5") (pintype "input"))
      (node (ref "U11") (pin "6") (pinfunction "~{SLEEP}_6") (pintype "input"))
    )
    (net (code "156") (name "Net-(U12-DIR)") (class "Default")
      (node (ref "JP16") (pin "2") (pinfunction "2_2") (pintype "passive"))
      (node (ref "U12") (pin "8") (pinfunction "DIR_8") (pintype "input"))
    )
    (net (code "157") (name "Net-(U12-MS1)") (class "Default")
      (node (ref "SW12") (pin "1") (pinfunction "1_1") (pintype "passive"))
      (node (ref "U12") (pin "2") (pinfunction "MS1_2") (pintype "input"))
    )
    (net (code "158") (name "Net-(U12-MS2)") (class "Default")
      (node (ref "SW12") (pin "2") (pinfunction "2_2") (pintype "passive"))
      (node (ref "U12") (pin "3") (pinfunction "MS2_3") (pintype "input"))
    )
    (net (code "159") (name "Net-(U12-MS3)") (class "Default")
      (node (ref "SW12") (pin "3") (pinfunction "3_3") (pintype "passive"))
      (node (ref "U12") (pin "4") (pinfunction "MS3_4") (pintype "input"))
    )
    (net (code "160") (name "Net-(U12-STEP)") (class "Default")
      (node (ref "JP16") (pin "3") (pinfunction "3_3") (pintype "passive"))
      (node (ref "U12") (pin "7") (pinfunction "STEP_7") (pintype "input"))
    )
    (net (code "161") (name "Net-(U12-~{ENABLE})") (class "Default")
      (node (ref "JP17") (pin "1") (pinfunction "1_1") (pintype "passive"))
      (node (ref "R42") (pin "2") (pinfunction "2_2") (pintype "passive"))
      (node (ref "U12") (pin "1") (pinfunction "~{ENABLE}_1") (pintype "input"))
    )
    (net (code "162") (name "Net-(U12-~{RESET})") (class "Default")
      (node (ref "JP16") (pin "4") (pinfunction "4_4") (pintype "passive"))
      (node (ref "U12") (pin "5") (pinfunction "~{RESET}_5") (pintype "input"))
      (node (ref "U12") (pin "6") (pinfunction "~{SLEEP}_6") (pintype "input"))
    )
    (net (code "163") (name "Net-(U13-DIR)") (class "Default")
      (node (ref "JP1") (pin "7") (pinfunction "7_7") (pintype "passive"))
      (node (ref "U13") (pin "8") (pinfunction "DIR_8") (pintype "input"))
    )
    (net (code "164") (name "Net-(U13-MS1)") (class "Default")
      (node (ref "SW13") (pin "1") (pinfunction "1_1") (pintype "passive"))
      (node (ref "U13") (pin "2") (pinfunction "MS1_2") (pintype "input"))
    )
    (net (code "165") (name "Net-(U13-MS2)") (class "Default")
      (node (ref "SW13") (pin "2") (pinfunction "2_2") (pintype "passive"))
      (node (ref "U13") (pin "3") (pinfunction "MS2_3") (pintype "input"))
    )
    (net (code "166") (name "Net-(U13-MS3)") (class "Default")
      (node (ref "SW13") (pin "3") (pinfunction "3_3") (pintype "passive"))
      (node (ref "U13") (pin "4") (pinfunction "MS3_4") (pintype "input"))
    )
    (net (code "167") (name "Net-(U13-STEP)") (class "Default")
      (node (ref "JP1") (pin "8") (pinfunction "8_8") (pintype "passive"))
      (node (ref "U13") (pin "7") (pinfunction "STEP_7") (pintype "input"))
    )
    (net (code "168") (name "Net-(U13-~{ENABLE})") (class "Default")
      (node (ref "JP18") (pin "1") (pinfunction "1_1") (pintype "passive"))
      (node (ref "R43") (pin "2") (pinfunction "2_2") (pintype "passive"))
      (node (ref "U13") (pin "1") (pinfunction "~{ENABLE}_1") (pintype "input"))
    )
    (net (code "169") (name "Net-(U13-~{RESET})") (class "Default")
      (node (ref "JP16") (pin "1") (pinfunction "1_1") (pintype "passive"))
      (node (ref "U13") (pin "5") (pinfunction "~{RESET}_5") (pintype "input"))
      (node (ref "U13") (pin "6") (pinfunction "~{SLEEP}_6") (pintype "input"))
    )
    (net (code "170") (name "Net-(U14-DIR)") (class "Default")
      (node (ref "JP1") (pin "4") (pinfunction "4_4") (pintype "passive"))
      (node (ref "U14") (pin "8") (pinfunction "DIR_8") (pintype "input"))
    )
    (net (code "171") (name "Net-(U14-MS1)") (class "Default")
      (node (ref "SW14") (pin "1") (pinfunction "1_1") (pintype "passive"))
      (node (ref "U14") (pin "2") (pinfunction "MS1_2") (pintype "input"))
    )
    (net (code "172") (name "Net-(U14-MS2)") (class "Default")
      (node (ref "SW14") (pin "2") (pinfunction "2_2") (pintype "passive"))
      (node (ref "U14") (pin "3") (pinfunction "MS2_3") (pintype "input"))
    )
    (net (code "173") (name "Net-(U14-MS3)") (class "Default")
      (node (ref "SW14") (pin "3") (pinfunction "3_3") (pintype "passive"))
      (node (ref "U14") (pin "4") (pinfunction "MS3_4") (pintype "input"))
    )
    (net (code "174") (name "Net-(U14-STEP)") (class "Default")
      (node (ref "JP1") (pin "5") (pinfunction "5_5") (pintype "passive"))
      (node (ref "U14") (pin "7") (pinfunction "STEP_7") (pintype "input"))
    )
    (net (code "175") (name "Net-(U14-~{ENABLE})") (class "Default")
      (node (ref "JP19") (pin "1") (pinfunction "1_1") (pintype "passive"))
      (node (ref "R44") (pin "2") (pinfunction "2_2") (pintype "passive"))
      (node (ref "U14") (pin "1") (pinfunction "~{ENABLE}_1") (pintype "input"))
    )
    (net (code "176") (name "Net-(U14-~{RESET})") (class "Default")
      (node (ref "JP1") (pin "6") (pinfunction "6_6") (pintype "passive"))
      (node (ref "U14") (pin "5") (pinfunction "~{RESET}_5") (pintype "input"))
      (node (ref "U14") (pin "6") (pinfunction "~{SLEEP}_6") (pintype "input"))
    )
    (net (code "177") (name "Net-(U15-DIR)") (class "Default")
      (node (ref "JP1") (pin "1") (pinfunction "1_1") (pintype "passive"))
      (node (ref "U15") (pin "8") (pinfunction "DIR_8") (pintype "input"))
    )
    (net (code "178") (name "Net-(U15-MS1)") (class "Default")
      (node (ref "SW15") (pin "1") (pinfunction "1_1") (pintype "passive"))
      (node (ref "U15") (pin "2") (pinfunction "MS1_2") (pintype "input"))
    )
    (net (code "179") (name "Net-(U15-MS2)") (class "Default")
      (node (ref "SW15") (pin "2") (pinfunction "2_2") (pintype "passive"))
      (node (ref "U15") (pin "3") (pinfunction "MS2_3") (pintype "input"))
    )
    (net (code "180") (name "Net-(U15-MS3)") (class "Default")
      (node (ref "SW15") (pin "3") (pinfunction "3_3") (pintype "passive"))
      (node (ref "U15") (pin "4") (pinfunction "MS3_4") (pintype "input"))
    )
    (net (code "181") (name "Net-(U15-STEP)") (class "Default")
      (node (ref "JP1") (pin "2") (pinfunction "2_2") (pintype "passive"))
      (node (ref "U15") (pin "7") (pinfunction "STEP_7") (pintype "input"))
    )
    (net (code "182") (name "Net-(U15-~{ENABLE})") (class "Default")
      (node (ref "JP20") (pin "1") (pinfunction "1_1") (pintype "passive"))
      (node (ref "R45") (pin "2") (pinfunction "2_2") (pintype "passive"))
      (node (ref "U15") (pin "1") (pinfunction "~{ENABLE}_1") (pintype "input"))
    )
    (net (code "183") (name "Net-(U15-~{RESET})") (class "Default")
      (node (ref "JP1") (pin "3") (pinfunction "3_3") (pintype "passive"))
      (node (ref "U15") (pin "5") (pinfunction "~{RESET}_5") (pintype "input"))
      (node (ref "U15") (pin "6") (pinfunction "~{SLEEP}_6") (pintype "input"))
    )
    (net (code "184") (name "unconnected-(J1-Pad1)") (class "Default")
      (node (ref "J1") (pin "1") (pinfunction "1_1") (pintype "passive"))
    )
    (net (code "185") (name "unconnected-(J1-Pad2)") (class "Default")
      (node (ref "J1") (pin "2") (pinfunction "2_2") (pintype "passive"))
    )
    (net (code "186") (name "unconnected-(J1-Pad3)") (class "Default")
      (node (ref "J1") (pin "3") (pinfunction "3_3") (pintype "passive"))
    )
    (net (code "187") (name "unconnected-(J1-Pad4)") (class "Default")
      (node (ref "J1") (pin "4") (pinfunction "4_4") (pintype "passive"))
    )
    (net (code "188") (name "unconnected-(JP2-Pad1)") (class "Default")
      (node (ref "JP2") (pin "1") (pinfunction "1_1") (pintype "passive"))
    )
    (net (code "189") (name "unconnected-(JP2-Pad2)") (class "Default")
      (node (ref "JP2") (pin "2") (pinfunction "2_2") (pintype "passive"))
    )
    (net (code "190") (name "unconnected-(JP2-Pad3)") (class "Default")
      (node (ref "JP2") (pin "3") (pinfunction "3_3") (pintype "passive"))
    )
    (net (code "191") (name "unconnected-(JP2-Pad4)") (class "Default")
      (node (ref "JP2") (pin "4") (pinfunction "4_4") (pintype "passive"))
    )
    (net (code "192") (name "unconnected-(JP2-Pad8)") (class "Default")
      (node (ref "JP2") (pin "8") (pinfunction "8_8") (pintype "passive"))
    )
    (net (code "193") (name "unconnected-(JP3-Pad1)") (class "Default")
      (node (ref "JP3") (pin "1") (pinfunction "1_1") (pintype "passive"))
    )
    (net (code "194") (name "unconnected-(JP3-Pad2)") (class "Default")
      (node (ref "JP3") (pin "2") (pinfunction "2_2") (pintype "passive"))
    )
    (net (code "195") (name "unconnected-(JP3-Pad3)") (class "Default")
      (node (ref "JP3") (pin "3") (pinfunction "3_3") (pintype "passive"))
    )
    (net (code "196") (name "unconnected-(JP3-Pad4)") (class "Default")
      (node (ref "JP3") (pin "4") (pinfunction "4_4") (pintype "passive"))
    )
    (net (code "197") (name "unconnected-(JP3-Pad5)") (class "Default")
      (node (ref "JP3") (pin "5") (pinfunction "5_5") (pintype "passive"))
    )
    (net (code "198") (name "unconnected-(JP3-Pad6)") (class "Default")
      (node (ref "JP3") (pin "6") (pinfunction "6_6") (pintype "passive"))
    )
    (net (code "199") (name "unconnected-(JP3-Pad7)") (class "Default")
      (node (ref "JP3") (pin "7") (pinfunction "7_7") (pintype "passive"))
    )
    (net (code "200") (name "unconnected-(JP3-Pad8)") (class "Default")
      (node (ref "JP3") (pin "8") (pinfunction "8_8") (pintype "passive"))
    )
    (net (code "201") (name "unconnected-(JP4-Pad1)") (class "Default")
      (node (ref "JP4") (pin "1") (pinfunction "1_1") (pintype "passive"))
    )
    (net (code "202") (name "unconnected-(JP4-Pad2)") (class "Default")
      (node (ref "JP4") (pin "2") (pinfunction "2_2") (pintype "passive"))
    )
    (net (code "203") (name "unconnected-(JP4-Pad3)") (class "Default")
      (node (ref "JP4") (pin "3") (pinfunction "3_3") (pintype "passive"))
    )
    (net (code "204") (name "unconnected-(JP4-Pad4)") (class "Default")
      (node (ref "JP4") (pin "4") (pinfunction "4_4") (pintype "passive"))
    )
    (net (code "205") (name "unconnected-(JP4-Pad5)") (class "Default")
      (node (ref "JP4") (pin "5") (pinfunction "5_5") (pintype "passive"))
    )
    (net (code "206") (name "unconnected-(JP4-Pad6)") (class "Default")
      (node (ref "JP4") (pin "6") (pinfunction "6_6") (pintype "passive"))
    )
    (net (code "207") (name "unconnected-(JP4-Pad7)") (class "Default")
      (node (ref "JP4") (pin "7") (pinfunction "7_7") (pintype "passive"))
    )
    (net (code "208") (name "unconnected-(JP4-Pad8)") (class "Default")
      (node (ref "JP4") (pin "8") (pinfunction "8_8") (pintype "passive"))
    )
    (net (code "209") (name "unconnected-(JP16-Pad8)") (class "Default")
      (node (ref "JP16") (pin "8") (pinfunction "8_8") (pintype "passive"))
    )
    (net (code "210") (name "unconnected-(U$16-Pad1)") (class "Default")
      (node (ref "U$16") (pin "1") (pinfunction "1_1") (pintype "passive"))
    )
    (net (code "211") (name "unconnected-(U$16-Pad2)") (class "Default")
      (node (ref "U$16") (pin "2") (pinfunction "2_2") (pintype "passive"))
    )
    (net (code "212") (name "unconnected-(U$16-Pad3)") (class "Default")
      (node (ref "U$16") (pin "3") (pinfunction "3_3") (pintype "passive"))
    )
    (net (code "213") (name "unconnected-(U$16-Pad4)") (class "Default")
      (node (ref "U$16") (pin "4") (pinfunction "4_4") (pintype "passive"))
    )
    (net (code "214") (name "unconnected-(U$16-Pad5)") (class "Default")
      (node (ref "U$16") (pin "5") (pinfunction "5_5") (pintype "passive"))
    )
    (net (code "215") (name "unconnected-(U$16-Pad6)") (class "Default")
      (node (ref "U$16") (pin "6") (pinfunction "6_6") (pintype "passive"))
    )
    (net (code "216") (name "unconnected-(U$16-Pad7)") (class "Default")
      (node (ref "U$16") (pin "7") (pinfunction "7_7") (pintype "passive"))
    )
    (net (code "217") (name "unconnected-(U$16-Pad8)") (class "Default")
      (node (ref "U$16") (pin "8") (pinfunction "8_8") (pintype "passive"))
    )
    (net (code "218") (name "unconnected-(U$16-Pad9)") (class "Default")
      (node (ref "U$16") (pin "9") (pinfunction "9_9") (pintype "passive"))
    )
    (net (code "219") (name "unconnected-(U$16-Pad10)") (class "Default")
      (node (ref "U$16") (pin "10") (pinfunction "10_10") (pintype "passive"))
    )
  )
)
